# BE200_QUAD_Rev1.net
KiCad netlist of a schematic drawn in EAGLE
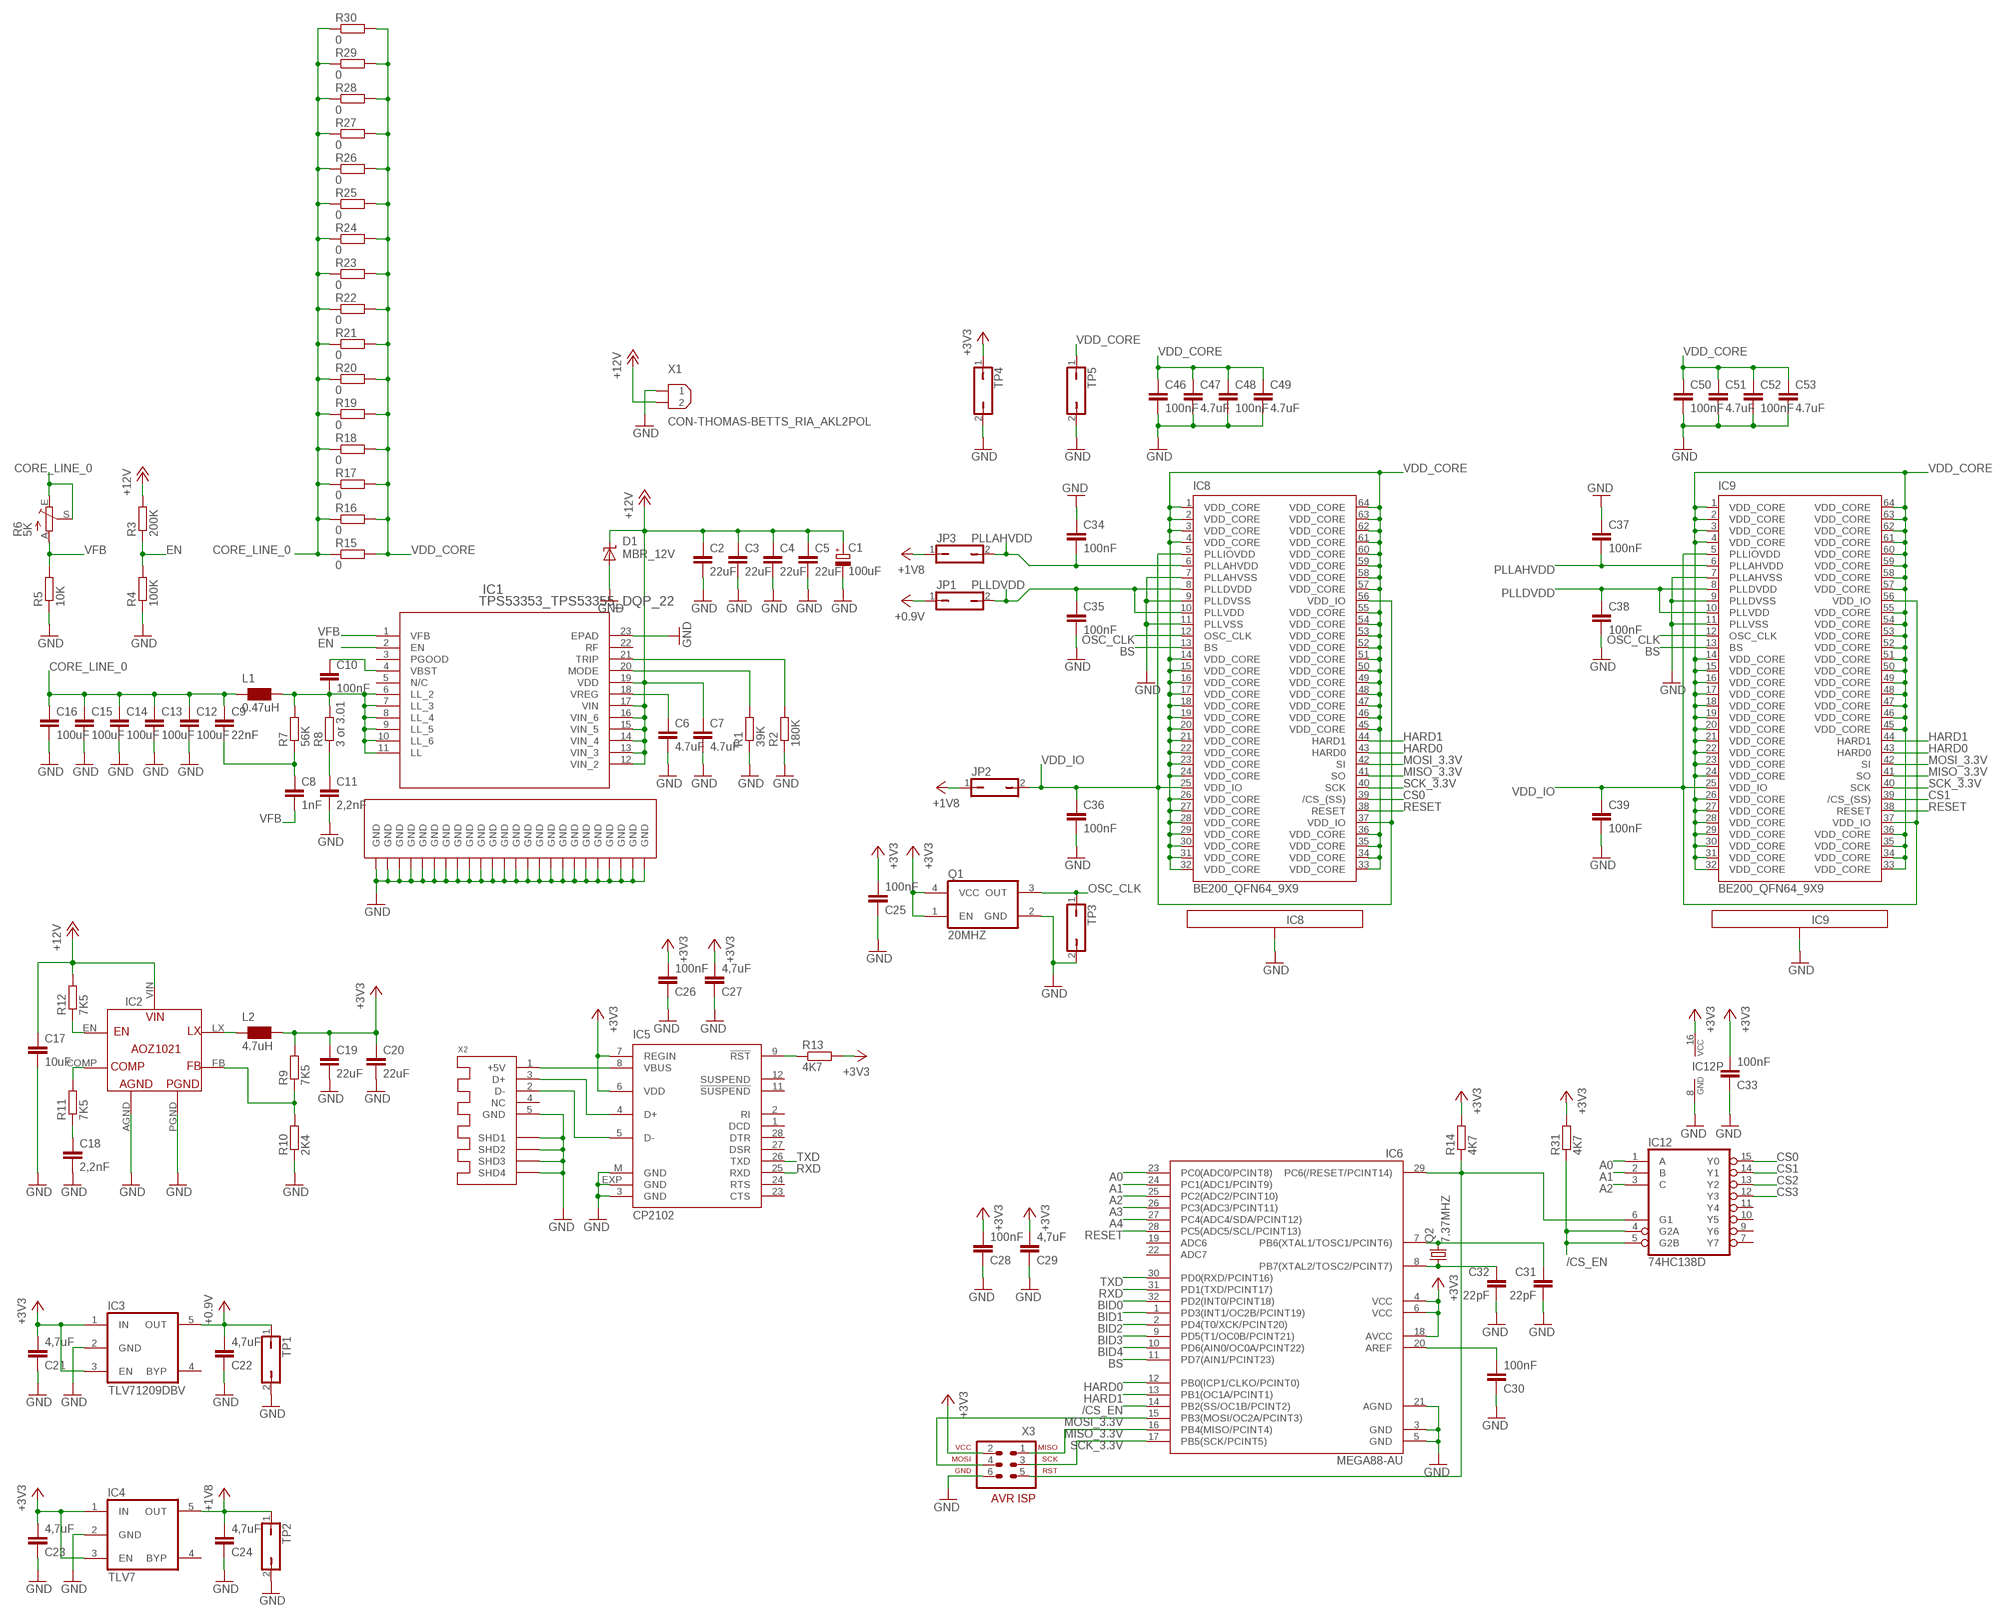
[diagram p0: schematic, sheet 1, part 1 of 2]
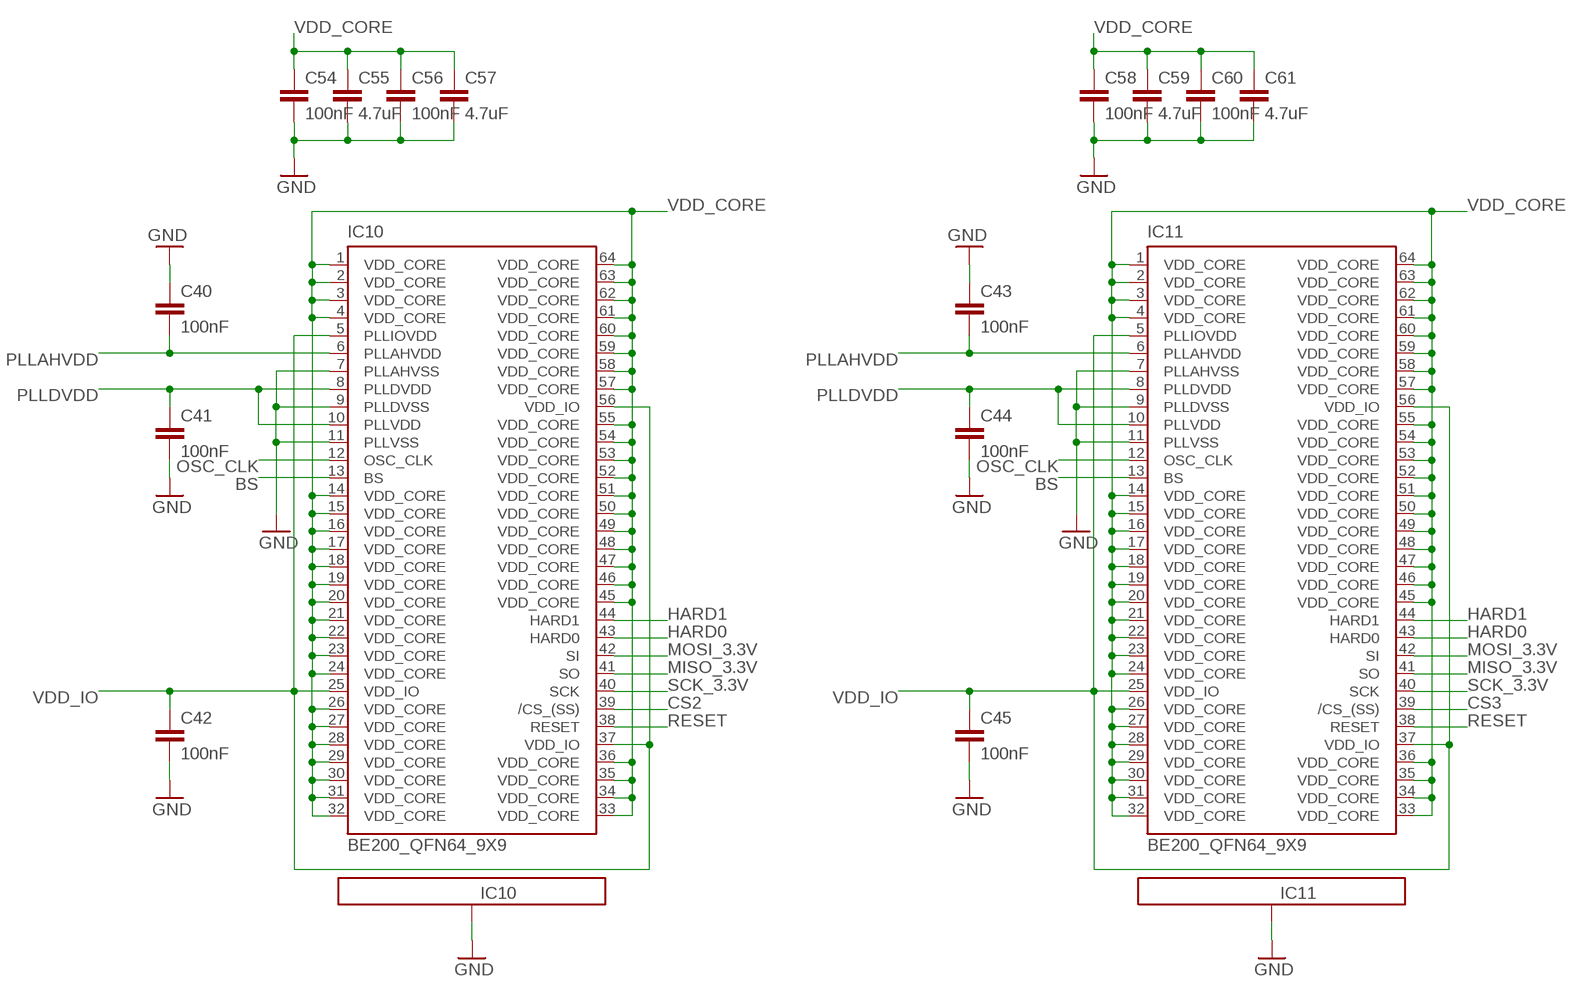
[diagram p1: schematic, sheet 1, part 2 of 2]

(export (version "E")
  (design (tool "Eeschema 10.0.6"))
  (components
    (comp (ref "C1")
      (value "100uF")
      (footprint "eagle-import:153CLV-0605")
      (libsource (lib "eagle-import") (part "CPOL-EU153CLV-0605"))
    )
    (comp (ref "C2")
      (value "22uF")
      (footprint "eagle-import:C1210K")
      (libsource (lib "eagle-import") (part "C-EUC1210K"))
    )
    (comp (ref "C3")
      (value "22uF")
      (footprint "eagle-import:C1210K")
      (libsource (lib "eagle-import") (part "C-EUC1210K"))
    )
    (comp (ref "C4")
      (value "22uF")
      (footprint "eagle-import:C1210K")
      (libsource (lib "eagle-import") (part "C-EUC1210K"))
    )
    (comp (ref "C5")
      (value "22uF")
      (footprint "eagle-import:C1210K")
      (libsource (lib "eagle-import") (part "C-EUC1210K"))
    )
    (comp (ref "C6")
      (value "4.7uF")
      (footprint "eagle-import:C0805K")
      (libsource (lib "eagle-import") (part "C-EUC0805K"))
    )
    (comp (ref "C7")
      (value "4.7uF")
      (footprint "eagle-import:C0805K")
      (libsource (lib "eagle-import") (part "C-EUC0805K"))
    )
    (comp (ref "C8")
      (value "1nF")
      (footprint "eagle-import:C0805K")
      (libsource (lib "eagle-import") (part "C-EUC0805K"))
    )
    (comp (ref "C9")
      (value "22nF")
      (footprint "eagle-import:C0805K")
      (libsource (lib "eagle-import") (part "C-EUC0805K"))
    )
    (comp (ref "C10")
      (value "100nF")
      (footprint "eagle-import:C0805K")
      (libsource (lib "eagle-import") (part "C-EUC0805K"))
    )
    (comp (ref "C11")
      (value "2,2nF")
      (footprint "eagle-import:C0805K")
      (libsource (lib "eagle-import") (part "C-EUC0805K"))
    )
    (comp (ref "C12")
      (value "100uF")
      (footprint "eagle-import:C1210K")
      (libsource (lib "eagle-import") (part "C-EUC1210K"))
    )
    (comp (ref "C13")
      (value "100uF")
      (footprint "eagle-import:C1210K")
      (libsource (lib "eagle-import") (part "C-EUC1210K"))
    )
    (comp (ref "C14")
      (value "100uF")
      (footprint "eagle-import:C1210K")
      (libsource (lib "eagle-import") (part "C-EUC1210K"))
    )
    (comp (ref "C15")
      (value "100uF")
      (footprint "eagle-import:C1210K")
      (libsource (lib "eagle-import") (part "C-EUC1210K"))
    )
    (comp (ref "C16")
      (value "100uF")
      (footprint "eagle-import:C1210K")
      (libsource (lib "eagle-import") (part "C-EUC1210K"))
    )
    (comp (ref "C17")
      (value "10uF")
      (footprint "eagle-import:C1206K")
      (libsource (lib "eagle-import") (part "C-EUC1206K"))
    )
    (comp (ref "C18")
      (value "2,2nF")
      (footprint "eagle-import:C0805K")
      (libsource (lib "eagle-import") (part "C-EUC0805K"))
    )
    (comp (ref "C19")
      (value "22uF")
      (footprint "eagle-import:C1206K")
      (libsource (lib "eagle-import") (part "C-EUC1206K"))
    )
    (comp (ref "C20")
      (value "22uF")
      (footprint "eagle-import:C1206K")
      (libsource (lib "eagle-import") (part "C-EUC1206K"))
    )
    (comp (ref "C21")
      (value "4,7uF")
      (footprint "eagle-import:C0805K")
      (libsource (lib "eagle-import") (part "C-EUC0805K"))
    )
    (comp (ref "C22")
      (value "4,7uF")
      (footprint "eagle-import:C0805K")
      (libsource (lib "eagle-import") (part "C-EUC0805K"))
    )
    (comp (ref "C23")
      (value "4,7uF")
      (footprint "eagle-import:C0805K")
      (libsource (lib "eagle-import") (part "C-EUC0805K"))
    )
    (comp (ref "C24")
      (value "4,7uF")
      (footprint "eagle-import:C0805K")
      (libsource (lib "eagle-import") (part "C-EUC0805K"))
    )
    (comp (ref "C25")
      (value "100nF")
      (footprint "eagle-import:C0805K")
      (libsource (lib "eagle-import") (part "C-EUC0805K"))
    )
    (comp (ref "C26")
      (value "100nF")
      (footprint "eagle-import:C0805K")
      (libsource (lib "eagle-import") (part "C-EUC0805K"))
    )
    (comp (ref "C27")
      (value "4,7uF")
      (footprint "eagle-import:C0805K")
      (libsource (lib "eagle-import") (part "C-EUC0805K"))
    )
    (comp (ref "C28")
      (value "100nF")
      (footprint "eagle-import:C0805K")
      (libsource (lib "eagle-import") (part "C-EUC0805K"))
    )
    (comp (ref "C29")
      (value "4,7uF")
      (footprint "eagle-import:C0805K")
      (libsource (lib "eagle-import") (part "C-EUC0805K"))
    )
    (comp (ref "C30")
      (value "100nF")
      (footprint "eagle-import:C0805K")
      (libsource (lib "eagle-import") (part "C-EUC0805K"))
    )
    (comp (ref "C31")
      (value "22pF")
      (footprint "eagle-import:C0805K")
      (libsource (lib "eagle-import") (part "C-EUC0805K"))
    )
    (comp (ref "C32")
      (value "22pF")
      (footprint "eagle-import:C0805K")
      (libsource (lib "eagle-import") (part "C-EUC0805K"))
    )
    (comp (ref "C33")
      (value "100nF")
      (footprint "eagle-import:C0805K")
      (libsource (lib "eagle-import") (part "C-EUC0805K"))
    )
    (comp (ref "C34")
      (value "100nF")
      (footprint "eagle-import:MYRCL_C0603K")
      (libsource (lib "eagle-import") (part "MYRCL_C-EUC0603K"))
    )
    (comp (ref "C35")
      (value "100nF")
      (footprint "eagle-import:MYRCL_C0603K")
      (libsource (lib "eagle-import") (part "MYRCL_C-EUC0603K"))
    )
    (comp (ref "C36")
      (value "100nF")
      (footprint "eagle-import:MYRCL_C0603K")
      (libsource (lib "eagle-import") (part "MYRCL_C-EUC0603K"))
    )
    (comp (ref "C37")
      (value "100nF")
      (footprint "eagle-import:MYRCL_C0603K")
      (libsource (lib "eagle-import") (part "MYRCL_C-EUC0603K"))
    )
    (comp (ref "C38")
      (value "100nF")
      (footprint "eagle-import:MYRCL_C0603K")
      (libsource (lib "eagle-import") (part "MYRCL_C-EUC0603K"))
    )
    (comp (ref "C39")
      (value "100nF")
      (footprint "eagle-import:MYRCL_C0603K")
      (libsource (lib "eagle-import") (part "MYRCL_C-EUC0603K"))
    )
    (comp (ref "C40")
      (value "100nF")
      (footprint "eagle-import:MYRCL_C0603K")
      (libsource (lib "eagle-import") (part "MYRCL_C-EUC0603K"))
    )
    (comp (ref "C41")
      (value "100nF")
      (footprint "eagle-import:MYRCL_C0603K")
      (libsource (lib "eagle-import") (part "MYRCL_C-EUC0603K"))
    )
    (comp (ref "C42")
      (value "100nF")
      (footprint "eagle-import:MYRCL_C0603K")
      (libsource (lib "eagle-import") (part "MYRCL_C-EUC0603K"))
    )
    (comp (ref "C43")
      (value "100nF")
      (footprint "eagle-import:MYRCL_C0603K")
      (libsource (lib "eagle-import") (part "MYRCL_C-EUC0603K"))
    )
    (comp (ref "C44")
      (value "100nF")
      (footprint "eagle-import:MYRCL_C0603K")
      (libsource (lib "eagle-import") (part "MYRCL_C-EUC0603K"))
    )
    (comp (ref "C45")
      (value "100nF")
      (footprint "eagle-import:MYRCL_C0603K")
      (libsource (lib "eagle-import") (part "MYRCL_C-EUC0603K"))
    )
    (comp (ref "C46")
      (value "100nF")
      (footprint "eagle-import:MYRCL_C0603K")
      (libsource (lib "eagle-import") (part "MYRCL_C-EUC0603K"))
    )
    (comp (ref "C47")
      (value "4.7uF")
      (footprint "eagle-import:MYRCL_C0603K")
      (libsource (lib "eagle-import") (part "MYRCL_C-EUC0603K"))
    )
    (comp (ref "C48")
      (value "100nF")
      (footprint "eagle-import:MYRCL_C0603K")
      (libsource (lib "eagle-import") (part "MYRCL_C-EUC0603K"))
    )
    (comp (ref "C49")
      (value "4.7uF")
      (footprint "eagle-import:MYRCL_C0603K")
      (libsource (lib "eagle-import") (part "MYRCL_C-EUC0603K"))
    )
    (comp (ref "C50")
      (value "100nF")
      (footprint "eagle-import:MYRCL_C0603K")
      (libsource (lib "eagle-import") (part "MYRCL_C-EUC0603K"))
    )
    (comp (ref "C51")
      (value "4.7uF")
      (footprint "eagle-import:MYRCL_C0603K")
      (libsource (lib "eagle-import") (part "MYRCL_C-EUC0603K"))
    )
    (comp (ref "C52")
      (value "100nF")
      (footprint "eagle-import:MYRCL_C0603K")
      (libsource (lib "eagle-import") (part "MYRCL_C-EUC0603K"))
    )
    (comp (ref "C53")
      (value "4.7uF")
      (footprint "eagle-import:MYRCL_C0603K")
      (libsource (lib "eagle-import") (part "MYRCL_C-EUC0603K"))
    )
    (comp (ref "C54")
      (value "100nF")
      (footprint "eagle-import:MYRCL_C0603K")
      (libsource (lib "eagle-import") (part "MYRCL_C-EUC0603K"))
    )
    (comp (ref "C55")
      (value "4.7uF")
      (footprint "eagle-import:MYRCL_C0603K")
      (libsource (lib "eagle-import") (part "MYRCL_C-EUC0603K"))
    )
    (comp (ref "C56")
      (value "100nF")
      (footprint "eagle-import:MYRCL_C0603K")
      (libsource (lib "eagle-import") (part "MYRCL_C-EUC0603K"))
    )
    (comp (ref "C57")
      (value "4.7uF")
      (footprint "eagle-import:MYRCL_C0603K")
      (libsource (lib "eagle-import") (part "MYRCL_C-EUC0603K"))
    )
    (comp (ref "C58")
      (value "100nF")
      (footprint "eagle-import:MYRCL_C0603K")
      (libsource (lib "eagle-import") (part "MYRCL_C-EUC0603K"))
    )
    (comp (ref "C59")
      (value "4.7uF")
      (footprint "eagle-import:MYRCL_C0603K")
      (libsource (lib "eagle-import") (part "MYRCL_C-EUC0603K"))
    )
    (comp (ref "C60")
      (value "100nF")
      (footprint "eagle-import:MYRCL_C0603K")
      (libsource (lib "eagle-import") (part "MYRCL_C-EUC0603K"))
    )
    (comp (ref "C61")
      (value "4.7uF")
      (footprint "eagle-import:MYRCL_C0603K")
      (libsource (lib "eagle-import") (part "MYRCL_C-EUC0603K"))
    )
    (comp (ref "D1")
      (value "MBR_12V")
      (footprint "eagle-import:SMBJ")
      (libsource (lib "eagle-import") (part "SUPPRESSOR-SMBJ"))
    )
    (comp (ref "IC1")
      (value "TPS53353_TPS53355_DQP_22")
      (footprint "eagle-import:DQP22_5P479X3P24")
      (fields
        (field (name "GENERIC_PART_NUMBER") "TPS53355")
        (field (name "MANUFACTURER") "Texas Instruments")
        (field (name "MANUFACTURER_PART_NUMBER") "tps53355_dqp_22")
      )
      (libsource (lib "eagle-import") (part "TPS53355_DQP_22"))
    )
    (comp (ref "IC2")
      (value "AOZ1021")
      (footprint "eagle-import:AOZ1021")
      (libsource (lib "eagle-import") (part "AOZ1021"))
    )
    (comp (ref "IC3")
      (value "TLV71209DBV")
      (footprint "eagle-import:SOT-23-5")
      (libsource (lib "eagle-import") (part "VREG_5PINS-SOT-23-5"))
    )
    (comp (ref "IC4")
      (value "TLV7")
      (footprint "eagle-import:SOT-23-5")
      (libsource (lib "eagle-import") (part "VREG_5PINS-SOT-23-5"))
    )
    (comp (ref "IC5")
      (value "CP2102")
      (footprint "eagle-import:SILABS2_MLP28")
      (libsource (lib "eagle-import") (part "SILABS2_CP2102"))
    )
    (comp (ref "IC6")
      (value "MEGA88-AU")
      (footprint "eagle-import:TQFP32-08")
      (libsource (lib "eagle-import") (part "MEGA48/88/168-AU"))
    )
    (comp (ref "IC8")
      (value "BE200_QFN64_9X9")
      (footprint "eagle-import:QFN64-9X9")
      (libsource (lib "eagle-import") (part "BE200_QFN64_9X9"))
    )
    (comp (ref "IC9")
      (value "BE200_QFN64_9X9")
      (footprint "eagle-import:QFN64-9X9")
      (libsource (lib "eagle-import") (part "BE200_QFN64_9X9"))
    )
    (comp (ref "IC10")
      (value "BE200_QFN64_9X9")
      (footprint "eagle-import:QFN64-9X9")
      (libsource (lib "eagle-import") (part "BE200_QFN64_9X9"))
    )
    (comp (ref "IC11")
      (value "BE200_QFN64_9X9")
      (footprint "eagle-import:QFN64-9X9")
      (libsource (lib "eagle-import") (part "BE200_QFN64_9X9"))
    )
    (comp (ref "IC12")
      (value "74HC138D")
      (footprint "eagle-import:SO16")
      (libsource (lib "eagle-import") (part "74138DHC"))
    )
    (comp (ref "JP1")
      (value "JP1Q")
      (footprint "eagle-import:JP1")
      (libsource (lib "eagle-import") (part "JP1Q"))
    )
    (comp (ref "JP2")
      (value "JP1Q")
      (footprint "eagle-import:JP1")
      (libsource (lib "eagle-import") (part "JP1Q"))
    )
    (comp (ref "JP3")
      (value "JP1Q")
      (footprint "eagle-import:JP1")
      (libsource (lib "eagle-import") (part "JP1Q"))
    )
    (comp (ref "L1")
      (value "0.47uH")
      (footprint "eagle-import:INDUCTOR_PA0513")
      (libsource (lib "eagle-import") (part "INDCUTOR_PA0513"))
    )
    (comp (ref "L2")
      (value "4.7uH")
      (footprint "eagle-import:INDCUCTOR_7.3X7.3")
      (libsource (lib "eagle-import") (part "INDUCTOR_7.3X7.3"))
    )
    (comp (ref "Q1")
      (value "20MHZ")
      (footprint "eagle-import:OSCILLATOR_7X5_SMD")
      (libsource (lib "eagle-import") (part "OSC-OSCILLATOR"))
    )
    (comp (ref "Q2")
      (value "7.37MHZ")
      (footprint "eagle-import:HC49UP")
      (libsource (lib "eagle-import") (part "CRYSTALHC49UP"))
    )
    (comp (ref "R1")
      (value "39K")
      (footprint "eagle-import:R0805K")
      (libsource (lib "eagle-import") (part "R-EU_R0805K"))
    )
    (comp (ref "R2")
      (value "180K")
      (footprint "eagle-import:R0805K")
      (libsource (lib "eagle-import") (part "R-EU_R0805K"))
    )
    (comp (ref "R3")
      (value "200K")
      (footprint "eagle-import:R0805K")
      (libsource (lib "eagle-import") (part "R-EU_R0805K"))
    )
    (comp (ref "R4")
      (value "100K")
      (footprint "eagle-import:R0805K")
      (libsource (lib "eagle-import") (part "R-EU_R0805K"))
    )
    (comp (ref "R5")
      (value "10K")
      (footprint "eagle-import:R0805K")
      (libsource (lib "eagle-import") (part "R-EU_R0805K"))
    )
    (comp (ref "R6")
      (value "5K")
      (footprint "eagle-import:S64W")
      (libsource (lib "eagle-import") (part "TRIM_EU-S64W"))
    )
    (comp (ref "R7")
      (value "56K")
      (footprint "eagle-import:R0805K")
      (libsource (lib "eagle-import") (part "R-EU_R0805K"))
    )
    (comp (ref "R8")
      (value "3 or 3.01")
      (footprint "eagle-import:R0805K")
      (libsource (lib "eagle-import") (part "R-EU_R0805K"))
    )
    (comp (ref "R9")
      (value "7K5")
      (footprint "eagle-import:R0805K")
      (libsource (lib "eagle-import") (part "R-EU_R0805K"))
    )
    (comp (ref "R10")
      (value "2K4")
      (footprint "eagle-import:R0805K")
      (libsource (lib "eagle-import") (part "R-EU_R0805K"))
    )
    (comp (ref "R11")
      (value "7K5")
      (footprint "eagle-import:R0805K")
      (libsource (lib "eagle-import") (part "R-EU_R0805K"))
    )
    (comp (ref "R12")
      (value "7K5")
      (footprint "eagle-import:R0805K")
      (libsource (lib "eagle-import") (part "R-EU_R0805K"))
    )
    (comp (ref "R13")
      (value "4K7")
      (footprint "eagle-import:R0805K")
      (libsource (lib "eagle-import") (part "R-EU_R0805K"))
    )
    (comp (ref "R14")
      (value "4K7")
      (footprint "eagle-import:R0805K")
      (libsource (lib "eagle-import") (part "R-EU_R0805K"))
    )
    (comp (ref "R15")
      (value "0")
      (footprint "eagle-import:R0805K")
      (libsource (lib "eagle-import") (part "R-EU_R0805K"))
    )
    (comp (ref "R16")
      (value "0")
      (footprint "eagle-import:R0805K")
      (libsource (lib "eagle-import") (part "R-EU_R0805K"))
    )
    (comp (ref "R17")
      (value "0")
      (footprint "eagle-import:R0805K")
      (libsource (lib "eagle-import") (part "R-EU_R0805K"))
    )
    (comp (ref "R18")
      (value "0")
      (footprint "eagle-import:R0805K")
      (libsource (lib "eagle-import") (part "R-EU_R0805K"))
    )
    (comp (ref "R19")
      (value "0")
      (footprint "eagle-import:R0805K")
      (libsource (lib "eagle-import") (part "R-EU_R0805K"))
    )
    (comp (ref "R20")
      (value "0")
      (footprint "eagle-import:R0805K")
      (libsource (lib "eagle-import") (part "R-EU_R0805K"))
    )
    (comp (ref "R21")
      (value "0")
      (footprint "eagle-import:R0805K")
      (libsource (lib "eagle-import") (part "R-EU_R0805K"))
    )
    (comp (ref "R22")
      (value "0")
      (footprint "eagle-import:R0805K")
      (libsource (lib "eagle-import") (part "R-EU_R0805K"))
    )
    (comp (ref "R23")
      (value "0")
      (footprint "eagle-import:R0805K")
      (libsource (lib "eagle-import") (part "R-EU_R0805K"))
    )
    (comp (ref "R24")
      (value "0")
      (footprint "eagle-import:R0805K")
      (libsource (lib "eagle-import") (part "R-EU_R0805K"))
    )
    (comp (ref "R25")
      (value "0")
      (footprint "eagle-import:R0805K")
      (libsource (lib "eagle-import") (part "R-EU_R0805K"))
    )
    (comp (ref "R26")
      (value "0")
      (footprint "eagle-import:R0805K")
      (libsource (lib "eagle-import") (part "R-EU_R0805K"))
    )
    (comp (ref "R27")
      (value "0")
      (footprint "eagle-import:R0805K")
      (libsource (lib "eagle-import") (part "R-EU_R0805K"))
    )
    (comp (ref "R28")
      (value "0")
      (footprint "eagle-import:R0805K")
      (libsource (lib "eagle-import") (part "R-EU_R0805K"))
    )
    (comp (ref "R29")
      (value "0")
      (footprint "eagle-import:R0805K")
      (libsource (lib "eagle-import") (part "R-EU_R0805K"))
    )
    (comp (ref "R30")
      (value "0")
      (footprint "eagle-import:R0805K")
      (libsource (lib "eagle-import") (part "R-EU_R0805K"))
    )
    (comp (ref "R31")
      (value "4K7")
      (footprint "eagle-import:R0805K")
      (libsource (lib "eagle-import") (part "R-EU_R0805K"))
    )
    (comp (ref "TP1")
      (value "JP1Q")
      (footprint "eagle-import:JP1")
      (libsource (lib "eagle-import") (part "JP1Q"))
    )
    (comp (ref "TP2")
      (value "JP1Q")
      (footprint "eagle-import:JP1")
      (libsource (lib "eagle-import") (part "JP1Q"))
    )
    (comp (ref "TP3")
      (value "JP1Q")
      (footprint "eagle-import:JP1")
      (libsource (lib "eagle-import") (part "JP1Q"))
    )
    (comp (ref "TP4")
      (value "JP1Q")
      (footprint "eagle-import:JP1")
      (libsource (lib "eagle-import") (part "JP1Q"))
    )
    (comp (ref "TP5")
      (value "JP1Q")
      (footprint "eagle-import:JP1")
      (libsource (lib "eagle-import") (part "JP1Q"))
    )
    (comp (ref "X1")
      (value "CON-THOMAS-BETTS_RIA_AKL2POL")
      (footprint "eagle-import:CON-THOMAS-BETTS_RIA_AKL2POL")
      (libsource (lib "eagle-import") (part "CON-THOMAS-BETTS_RIA_AKL2POL"))
    )
    (comp (ref "X2")
      (value "MYSTUFF_USB-MINI-ASSMANN")
      (footprint "eagle-import:MYSTUFF_USB_MINI-ASSMANN")
      (libsource (lib "eagle-import") (part "MYSTUFF_USB-MINI-ASSMANN"))
    )
    (comp (ref "X3")
      (value "AVR-ISP-6VERT")
      (footprint "eagle-import:AVR-ISP-6")
      (libsource (lib "eagle-import") (part "AVR-ISP-6VERT"))
    )
  )
  (nets
    (net (code "1") (name "+0.9V") (class "Default")
      (node (ref "C22") (pin "2") (pinfunction "2_2") (pintype "passive"))
      (node (ref "IC3") (pin "5") (pinfunction "OUT_5") (pintype "bidirectional"))
      (node (ref "JP1") (pin "1") (pinfunction "1_1") (pintype "passive"))
      (node (ref "TP1") (pin "1") (pinfunction "1_1") (pintype "passive"))
    )
    (net (code "2") (name "+1V8") (class "Default")
      (node (ref "C24") (pin "2") (pinfunction "2_2") (pintype "passive"))
      (node (ref "IC4") (pin "5") (pinfunction "OUT_5") (pintype "bidirectional"))
      (node (ref "JP2") (pin "1") (pinfunction "1_1") (pintype "passive"))
      (node (ref "JP3") (pin "1") (pinfunction "1_1") (pintype "passive"))
      (node (ref "TP2") (pin "1") (pinfunction "1_1") (pintype "passive"))
    )
    (net (code "3") (name "+3V3") (class "Default")
      (node (ref "C19") (pin "1") (pinfunction "1_1") (pintype "passive"))
      (node (ref "C20") (pin "1") (pinfunction "1_1") (pintype "passive"))
      (node (ref "C21") (pin "2") (pinfunction "2_2") (pintype "passive"))
      (node (ref "C23") (pin "2") (pinfunction "2_2") (pintype "passive"))
      (node (ref "C25") (pin "2") (pinfunction "2_2") (pintype "passive"))
      (node (ref "C26") (pin "2") (pinfunction "2_2") (pintype "passive"))
      (node (ref "C27") (pin "2") (pinfunction "2_2") (pintype "passive"))
      (node (ref "C28") (pin "2") (pinfunction "2_2") (pintype "passive"))
      (node (ref "C29") (pin "2") (pinfunction "2_2") (pintype "passive"))
      (node (ref "C33") (pin "2") (pinfunction "2_2") (pintype "passive"))
      (node (ref "IC12") (pin "16") (pinfunction "VCC_16") (pintype "power_in"))
      (node (ref "IC3") (pin "1") (pinfunction "IN_1") (pintype "bidirectional"))
      (node (ref "IC3") (pin "3") (pinfunction "EN_3") (pintype "bidirectional"))
      (node (ref "IC4") (pin "1") (pinfunction "IN_1") (pintype "bidirectional"))
      (node (ref "IC4") (pin "3") (pinfunction "EN_3") (pintype "bidirectional"))
      (node (ref "IC5") (pin "6") (pinfunction "VDD_6") (pintype "power_in"))
      (node (ref "IC5") (pin "7") (pinfunction "REGIN_7") (pintype "passive"))
      (node (ref "IC6") (pin "18") (pinfunction "AVCC_18") (pintype "passive"))
      (node (ref "IC6") (pin "4") (pinfunction "VCC_4") (pintype "power_in"))
      (node (ref "IC6") (pin "6") (pinfunction "VCC_6") (pintype "power_in"))
      (node (ref "L2") (pin "2") (pinfunction "2_2") (pintype "passive"))
      (node (ref "Q1") (pin "1") (pinfunction "EN_1") (pintype "input"))
      (node (ref "Q1") (pin "4") (pinfunction "VCC_4") (pintype "power_in"))
      (node (ref "R13") (pin "2") (pinfunction "2_2") (pintype "passive"))
      (node (ref "R14") (pin "2") (pinfunction "2_2") (pintype "passive"))
      (node (ref "R31") (pin "2") (pinfunction "2_2") (pintype "passive"))
      (node (ref "R9") (pin "2") (pinfunction "2_2") (pintype "passive"))
      (node (ref "TP4") (pin "1") (pinfunction "1_1") (pintype "passive"))
      (node (ref "X3") (pin "2") (pinfunction "2_2") (pintype "passive"))
    )
    (net (code "4") (name "+12V") (class "Default")
      (node (ref "C1") (pin "+") (pinfunction "+_+") (pintype "passive"))
      (node (ref "C17") (pin "1") (pinfunction "1_1") (pintype "passive"))
      (node (ref "C2") (pin "1") (pinfunction "1_1") (pintype "passive"))
      (node (ref "C3") (pin "1") (pinfunction "1_1") (pintype "passive"))
      (node (ref "C4") (pin "1") (pinfunction "1_1") (pintype "passive"))
      (node (ref "C5") (pin "1") (pinfunction "1_1") (pintype "passive"))
      (node (ref "C7") (pin "1") (pinfunction "1_1") (pintype "passive"))
      (node (ref "D1") (pin "C") (pinfunction "C_C") (pintype "passive"))
      (node (ref "IC1") (pin "12") (pinfunction "VIN_2_12") (pintype "input"))
      (node (ref "IC1") (pin "13") (pinfunction "VIN_3_13") (pintype "input"))
      (node (ref "IC1") (pin "14") (pinfunction "VIN_4_14") (pintype "input"))
      (node (ref "IC1") (pin "15") (pinfunction "VIN_5_15") (pintype "input"))
      (node (ref "IC1") (pin "16") (pinfunction "VIN_6_16") (pintype "input"))
      (node (ref "IC1") (pin "17") (pinfunction "VIN_17") (pintype "input"))
      (node (ref "IC1") (pin "19") (pinfunction "VDD_19") (pintype "power_in"))
      (node (ref "IC2") (pin "VIN") (pinfunction "VIN_VIN") (pintype "bidirectional"))
      (node (ref "R12") (pin "2") (pinfunction "2_2") (pintype "passive"))
      (node (ref "R3") (pin "2") (pinfunction "2_2") (pintype "passive"))
      (node (ref "X1") (pin "2") (pinfunction "2_2") (pintype "passive"))
    )
    (net (code "5") (name "/A0") (class "Default")
      (node (ref "IC12") (pin "1") (pinfunction "A_1") (pintype "input"))
      (node (ref "IC6") (pin "23") (pinfunction "PC0(ADC0/PCINT8)_23") (pintype "bidirectional"))
    )
    (net (code "6") (name "/A1") (class "Default")
      (node (ref "IC12") (pin "2") (pinfunction "B_2") (pintype "input"))
      (node (ref "IC6") (pin "24") (pinfunction "PC1(ADC1/PCINT9)_24") (pintype "bidirectional"))
    )
    (net (code "7") (name "/A2") (class "Default")
      (node (ref "IC12") (pin "3") (pinfunction "C_3") (pintype "input"))
      (node (ref "IC6") (pin "25") (pinfunction "PC2(ADC2/PCINT10)_25") (pintype "bidirectional"))
    )
    (net (code "8") (name "/A3") (class "Default")
      (node (ref "IC6") (pin "26") (pinfunction "PC3(ADC3/PCINT11)_26") (pintype "bidirectional"))
    )
    (net (code "9") (name "/A4") (class "Default")
      (node (ref "IC6") (pin "27") (pinfunction "PC4(ADC4/SDA/PCINT12)_27") (pintype "bidirectional"))
    )
    (net (code "10") (name "/BID0") (class "Default")
      (node (ref "IC6") (pin "32") (pinfunction "PD2(INT0/PCINT18)_32") (pintype "bidirectional"))
    )
    (net (code "11") (name "/BID1") (class "Default")
      (node (ref "IC6") (pin "1") (pinfunction "PD3(INT1/OC2B/PCINT19)_1") (pintype "bidirectional"))
    )
    (net (code "12") (name "/BID2") (class "Default")
      (node (ref "IC6") (pin "2") (pinfunction "PD4(T0/XCK/PCINT20)_2") (pintype "bidirectional"))
    )
    (net (code "13") (name "/BID3") (class "Default")
      (node (ref "IC6") (pin "9") (pinfunction "PD5(T1/OC0B/PCINT21)_9") (pintype "bidirectional"))
    )
    (net (code "14") (name "/BID4") (class "Default")
      (node (ref "IC6") (pin "10") (pinfunction "PD6(AIN0/OC0A/PCINT22)_10") (pintype "bidirectional"))
    )
    (net (code "15") (name "/BS") (class "Default")
      (node (ref "IC10") (pin "13") (pinfunction "BS_13") (pintype "input"))
      (node (ref "IC11") (pin "13") (pinfunction "BS_13") (pintype "input"))
      (node (ref "IC6") (pin "11") (pinfunction "PD7(AIN1/PCINT23)_11") (pintype "bidirectional"))
      (node (ref "IC8") (pin "13") (pinfunction "BS_13") (pintype "input"))
      (node (ref "IC9") (pin "13") (pinfunction "BS_13") (pintype "input"))
    )
    (net (code "16") (name "/CORE_LINE_0") (class "Default")
      (node (ref "C12") (pin "1") (pinfunction "1_1") (pintype "passive"))
      (node (ref "C13") (pin "1") (pinfunction "1_1") (pintype "passive"))
      (node (ref "C14") (pin "1") (pinfunction "1_1") (pintype "passive"))
      (node (ref "C15") (pin "1") (pinfunction "1_1") (pintype "passive"))
      (node (ref "C16") (pin "1") (pinfunction "1_1") (pintype "passive"))
      (node (ref "C9") (pin "1") (pinfunction "1_1") (pintype "passive"))
      (node (ref "L1") (pin "1") (pinfunction "1_1") (pintype "passive"))
      (node (ref "R15") (pin "1") (pinfunction "1_1") (pintype "passive"))
      (node (ref "R16") (pin "1") (pinfunction "1_1") (pintype "passive"))
      (node (ref "R17") (pin "1") (pinfunction "1_1") (pintype "passive"))
      (node (ref "R18") (pin "1") (pinfunction "1_1") (pintype "passive"))
      (node (ref "R19") (pin "1") (pinfunction "1_1") (pintype "passive"))
      (node (ref "R20") (pin "1") (pinfunction "1_1") (pintype "passive"))
      (node (ref "R21") (pin "1") (pinfunction "1_1") (pintype "passive"))
      (node (ref "R22") (pin "1") (pinfunction "1_1") (pintype "passive"))
      (node (ref "R23") (pin "1") (pinfunction "1_1") (pintype "passive"))
      (node (ref "R24") (pin "1") (pinfunction "1_1") (pintype "passive"))
      (node (ref "R25") (pin "1") (pinfunction "1_1") (pintype "passive"))
      (node (ref "R26") (pin "1") (pinfunction "1_1") (pintype "passive"))
      (node (ref "R27") (pin "1") (pinfunction "1_1") (pintype "passive"))
      (node (ref "R28") (pin "1") (pinfunction "1_1") (pintype "passive"))
      (node (ref "R29") (pin "1") (pinfunction "1_1") (pintype "passive"))
      (node (ref "R30") (pin "1") (pinfunction "1_1") (pintype "passive"))
      (node (ref "R6") (pin "E") (pinfunction "E_E") (pintype "passive"))
      (node (ref "R6") (pin "S") (pinfunction "S_S") (pintype "passive"))
    )
    (net (code "17") (name "/CS0") (class "Default")
      (node (ref "IC12") (pin "15") (pinfunction "Y0_15") (pintype "output"))
      (node (ref "IC8") (pin "39") (pinfunction "/CS_(SS)_39") (pintype "input"))
    )
    (net (code "18") (name "/CS1") (class "Default")
      (node (ref "IC12") (pin "14") (pinfunction "Y1_14") (pintype "output"))
      (node (ref "IC9") (pin "39") (pinfunction "/CS_(SS)_39") (pintype "input"))
    )
    (net (code "19") (name "/CS2") (class "Default")
      (node (ref "IC10") (pin "39") (pinfunction "/CS_(SS)_39") (pintype "input"))
      (node (ref "IC12") (pin "13") (pinfunction "Y2_13") (pintype "output"))
    )
    (net (code "20") (name "/CS3") (class "Default")
      (node (ref "IC11") (pin "39") (pinfunction "/CS_(SS)_39") (pintype "input"))
      (node (ref "IC12") (pin "12") (pinfunction "Y3_12") (pintype "output"))
    )
    (net (code "21") (name "/EN") (class "Default")
      (node (ref "IC1") (pin "2") (pinfunction "EN_2") (pintype "input"))
      (node (ref "R3") (pin "1") (pinfunction "1_1") (pintype "passive"))
      (node (ref "R4") (pin "2") (pinfunction "2_2") (pintype "passive"))
    )
    (net (code "22") (name "/HARD0") (class "Default")
      (node (ref "IC10") (pin "43") (pinfunction "HARD0_43") (pintype "input"))
      (node (ref "IC11") (pin "43") (pinfunction "HARD0_43") (pintype "input"))
      (node (ref "IC6") (pin "12") (pinfunction "PB0(ICP1/CLKO/PCINT0)_12") (pintype "bidirectional"))
      (node (ref "IC8") (pin "43") (pinfunction "HARD0_43") (pintype "input"))
      (node (ref "IC9") (pin "43") (pinfunction "HARD0_43") (pintype "input"))
    )
    (net (code "23") (name "/HARD1") (class "Default")
      (node (ref "IC10") (pin "44") (pinfunction "HARD1_44") (pintype "input"))
      (node (ref "IC11") (pin "44") (pinfunction "HARD1_44") (pintype "input"))
      (node (ref "IC6") (pin "13") (pinfunction "PB1(OC1A/PCINT1)_13") (pintype "bidirectional"))
      (node (ref "IC8") (pin "44") (pinfunction "HARD1_44") (pintype "input"))
      (node (ref "IC9") (pin "44") (pinfunction "HARD1_44") (pintype "input"))
    )
    (net (code "24") (name "/MISO_3.3V") (class "Default")
      (node (ref "IC10") (pin "41") (pinfunction "SO_41") (pintype "input"))
      (node (ref "IC11") (pin "41") (pinfunction "SO_41") (pintype "input"))
      (node (ref "IC6") (pin "16") (pinfunction "PB4(MISO/PCINT4)_16") (pintype "bidirectional"))
      (node (ref "IC8") (pin "41") (pinfunction "SO_41") (pintype "input"))
      (node (ref "IC9") (pin "41") (pinfunction "SO_41") (pintype "input"))
      (node (ref "X3") (pin "1") (pinfunction "1_1") (pintype "passive"))
    )
    (net (code "25") (name "/MOSI_3.3V") (class "Default")
      (node (ref "IC10") (pin "42") (pinfunction "SI_42") (pintype "input"))
      (node (ref "IC11") (pin "42") (pinfunction "SI_42") (pintype "input"))
      (node (ref "IC6") (pin "15") (pinfunction "PB3(MOSI/OC2A/PCINT3)_15") (pintype "bidirectional"))
      (node (ref "IC8") (pin "42") (pinfunction "SI_42") (pintype "input"))
      (node (ref "IC9") (pin "42") (pinfunction "SI_42") (pintype "input"))
      (node (ref "X3") (pin "4") (pinfunction "4_4") (pintype "passive"))
    )
    (net (code "26") (name "/OSC_CLK") (class "Default")
      (node (ref "IC10") (pin "12") (pinfunction "OSC_CLK_12") (pintype "input"))
      (node (ref "IC11") (pin "12") (pinfunction "OSC_CLK_12") (pintype "input"))
      (node (ref "IC8") (pin "12") (pinfunction "OSC_CLK_12") (pintype "input"))
      (node (ref "IC9") (pin "12") (pinfunction "OSC_CLK_12") (pintype "input"))
      (node (ref "Q1") (pin "3") (pinfunction "OUT_3") (pintype "output"))
      (node (ref "TP3") (pin "1") (pinfunction "1_1") (pintype "passive"))
    )
    (net (code "27") (name "/PLLAHVDD") (class "Default")
      (node (ref "C34") (pin "2") (pinfunction "2_2") (pintype "passive"))
      (node (ref "C37") (pin "2") (pinfunction "2_2") (pintype "passive"))
      (node (ref "C40") (pin "2") (pinfunction "2_2") (pintype "passive"))
      (node (ref "C43") (pin "2") (pinfunction "2_2") (pintype "passive"))
      (node (ref "IC10") (pin "6") (pinfunction "PLLAHVDD_6") (pintype "power_in"))
      (node (ref "IC11") (pin "6") (pinfunction "PLLAHVDD_6") (pintype "power_in"))
      (node (ref "IC8") (pin "6") (pinfunction "PLLAHVDD_6") (pintype "power_in"))
      (node (ref "IC9") (pin "6") (pinfunction "PLLAHVDD_6") (pintype "power_in"))
      (node (ref "JP3") (pin "2") (pinfunction "2_2") (pintype "passive"))
    )
    (net (code "28") (name "/PLLDVDD") (class "Default")
      (node (ref "C35") (pin "1") (pinfunction "1_1") (pintype "passive"))
      (node (ref "C38") (pin "1") (pinfunction "1_1") (pintype "passive"))
      (node (ref "C41") (pin "1") (pinfunction "1_1") (pintype "passive"))
      (node (ref "C44") (pin "1") (pinfunction "1_1") (pintype "passive"))
      (node (ref "IC10") (pin "10") (pinfunction "PLLVDD_10") (pintype "power_in"))
      (node (ref "IC10") (pin "8") (pinfunction "PLLDVDD_8") (pintype "power_in"))
      (node (ref "IC11") (pin "10") (pinfunction "PLLVDD_10") (pintype "power_in"))
      (node (ref "IC11") (pin "8") (pinfunction "PLLDVDD_8") (pintype "power_in"))
      (node (ref "IC8") (pin "10") (pinfunction "PLLVDD_10") (pintype "power_in"))
      (node (ref "IC8") (pin "8") (pinfunction "PLLDVDD_8") (pintype "power_in"))
      (node (ref "IC9") (pin "10") (pinfunction "PLLVDD_10") (pintype "power_in"))
      (node (ref "IC9") (pin "8") (pinfunction "PLLDVDD_8") (pintype "power_in"))
      (node (ref "JP1") (pin "2") (pinfunction "2_2") (pintype "passive"))
    )
    (net (code "29") (name "/RESET") (class "Default")
      (node (ref "IC10") (pin "38") (pinfunction "RESET_38") (pintype "input"))
      (node (ref "IC11") (pin "38") (pinfunction "RESET_38") (pintype "input"))
      (node (ref "IC6") (pin "28") (pinfunction "PC5(ADC5/SCL/PCINT13)_28") (pintype "bidirectional"))
      (node (ref "IC8") (pin "38") (pinfunction "RESET_38") (pintype "input"))
      (node (ref "IC9") (pin "38") (pinfunction "RESET_38") (pintype "input"))
    )
    (net (code "30") (name "/RXD") (class "Default")
      (node (ref "IC5") (pin "25") (pinfunction "RXD_25") (pintype "input"))
      (node (ref "IC6") (pin "31") (pinfunction "PD1(TXD/PCINT17)_31") (pintype "bidirectional"))
    )
    (net (code "31") (name "/SCK_3.3V") (class "Default")
      (node (ref "IC10") (pin "40") (pinfunction "SCK_40") (pintype "input"))
      (node (ref "IC11") (pin "40") (pinfunction "SCK_40") (pintype "input"))
      (node (ref "IC6") (pin "17") (pinfunction "PB5(SCK/PCINT5)_17") (pintype "bidirectional"))
      (node (ref "IC8") (pin "40") (pinfunction "SCK_40") (pintype "input"))
      (node (ref "IC9") (pin "40") (pinfunction "SCK_40") (pintype "input"))
      (node (ref "X3") (pin "3") (pinfunction "3_3") (pintype "passive"))
    )
    (net (code "32") (name "/TXD") (class "Default")
      (node (ref "IC5") (pin "26") (pinfunction "TXD_26") (pintype "output"))
      (node (ref "IC6") (pin "30") (pinfunction "PD0(RXD/PCINT16)_30") (pintype "bidirectional"))
    )
    (net (code "33") (name "/VDD_CORE") (class "Default")
      (node (ref "C46") (pin "1") (pinfunction "1_1") (pintype "passive"))
      (node (ref "C47") (pin "1") (pinfunction "1_1") (pintype "passive"))
      (node (ref "C48") (pin "1") (pinfunction "1_1") (pintype "passive"))
      (node (ref "C49") (pin "1") (pinfunction "1_1") (pintype "passive"))
      (node (ref "C50") (pin "1") (pinfunction "1_1") (pintype "passive"))
      (node (ref "C51") (pin "1") (pinfunction "1_1") (pintype "passive"))
      (node (ref "C52") (pin "1") (pinfunction "1_1") (pintype "passive"))
      (node (ref "C53") (pin "1") (pinfunction "1_1") (pintype "passive"))
      (node (ref "C54") (pin "1") (pinfunction "1_1") (pintype "passive"))
      (node (ref "C55") (pin "1") (pinfunction "1_1") (pintype "passive"))
      (node (ref "C56") (pin "1") (pinfunction "1_1") (pintype "passive"))
      (node (ref "C57") (pin "1") (pinfunction "1_1") (pintype "passive"))
      (node (ref "C58") (pin "1") (pinfunction "1_1") (pintype "passive"))
      (node (ref "C59") (pin "1") (pinfunction "1_1") (pintype "passive"))
      (node (ref "C60") (pin "1") (pinfunction "1_1") (pintype "passive"))
      (node (ref "C61") (pin "1") (pinfunction "1_1") (pintype "passive"))
      (node (ref "IC10") (pin "1") (pinfunction "VDD_CORE_1") (pintype "power_in"))
      (node (ref "IC10") (pin "14") (pinfunction "VDD_CORE_14") (pintype "power_in"))
      (node (ref "IC10") (pin "15") (pinfunction "VDD_CORE_15") (pintype "power_in"))
      (node (ref "IC10") (pin "16") (pinfunction "VDD_CORE_16") (pintype "power_in"))
      (node (ref "IC10") (pin "17") (pinfunction "VDD_CORE_17") (pintype "power_in"))
      (node (ref "IC10") (pin "18") (pinfunction "VDD_CORE_18") (pintype "power_in"))
      (node (ref "IC10") (pin "19") (pinfunction "VDD_CORE_19") (pintype "power_in"))
      (node (ref "IC10") (pin "2") (pinfunction "VDD_CORE_2") (pintype "power_in"))
      (node (ref "IC10") (pin "20") (pinfunction "VDD_CORE_20") (pintype "power_in"))
      (node (ref "IC10") (pin "21") (pinfunction "VDD_CORE_21") (pintype "power_in"))
      (node (ref "IC10") (pin "22") (pinfunction "VDD_CORE_22") (pintype "power_in"))
      (node (ref "IC10") (pin "23") (pinfunction "VDD_CORE_23") (pintype "power_in"))
      (node (ref "IC10") (pin "24") (pinfunction "VDD_CORE_24") (pintype "power_in"))
      (node (ref "IC10") (pin "26") (pinfunction "VDD_CORE_26") (pintype "power_in"))
      (node (ref "IC10") (pin "27") (pinfunction "VDD_CORE_27") (pintype "power_in"))
      (node (ref "IC10") (pin "28") (pinfunction "VDD_CORE_28") (pintype "power_in"))
      (node (ref "IC10") (pin "29") (pinfunction "VDD_CORE_29") (pintype "power_in"))
      (node (ref "IC10") (pin "3") (pinfunction "VDD_CORE_3") (pintype "power_in"))
      (node (ref "IC10") (pin "30") (pinfunction "VDD_CORE_30") (pintype "power_in"))
      (node (ref "IC10") (pin "31") (pinfunction "VDD_CORE_31") (pintype "power_in"))
      (node (ref "IC10") (pin "32") (pinfunction "VDD_CORE_32") (pintype "power_in"))
      (node (ref "IC10") (pin "33") (pinfunction "VDD_CORE_33") (pintype "power_in"))
      (node (ref "IC10") (pin "34") (pinfunction "VDD_CORE_34") (pintype "power_in"))
      (node (ref "IC10") (pin "35") (pinfunction "VDD_CORE_35") (pintype "power_in"))
      (node (ref "IC10") (pin "36") (pinfunction "VDD_CORE_36") (pintype "power_in"))
      (node (ref "IC10") (pin "4") (pinfunction "VDD_CORE_4") (pintype "power_in"))
      (node (ref "IC10") (pin "45") (pinfunction "VDD_CORE_45") (pintype "power_in"))
      (node (ref "IC10") (pin "46") (pinfunction "VDD_CORE_46") (pintype "power_in"))
      (node (ref "IC10") (pin "47") (pinfunction "VDD_CORE_47") (pintype "power_in"))
      (node (ref "IC10") (pin "48") (pinfunction "VDD_CORE_48") (pintype "power_in"))
      (node (ref "IC10") (pin "49") (pinfunction "VDD_CORE_49") (pintype "power_in"))
      (node (ref "IC10") (pin "50") (pinfunction "VDD_CORE_50") (pintype "power_in"))
      (node (ref "IC10") (pin "51") (pinfunction "VDD_CORE_51") (pintype "power_in"))
      (node (ref "IC10") (pin "52") (pinfunction "VDD_CORE_52") (pintype "power_in"))
      (node (ref "IC10") (pin "53") (pinfunction "VDD_CORE_53") (pintype "power_in"))
      (node (ref "IC10") (pin "54") (pinfunction "VDD_CORE_54") (pintype "power_in"))
      (node (ref "IC10") (pin "55") (pinfunction "VDD_CORE_55") (pintype "power_in"))
      (node (ref "IC10") (pin "57") (pinfunction "VDD_CORE_57") (pintype "power_in"))
      (node (ref "IC10") (pin "58") (pinfunction "VDD_CORE_58") (pintype "power_in"))
      (node (ref "IC10") (pin "59") (pinfunction "VDD_CORE_59") (pintype "power_in"))
      (node (ref "IC10") (pin "60") (pinfunction "VDD_CORE_60") (pintype "power_in"))
      (node (ref "IC10") (pin "61") (pinfunction "VDD_CORE_61") (pintype "power_in"))
      (node (ref "IC10") (pin "62") (pinfunction "VDD_CORE_62") (pintype "power_in"))
      (node (ref "IC10") (pin "63") (pinfunction "VDD_CORE_63") (pintype "power_in"))
      (node (ref "IC10") (pin "64") (pinfunction "VDD_CORE_64") (pintype "power_in"))
      (node (ref "IC11") (pin "1") (pinfunction "VDD_CORE_1") (pintype "power_in"))
      (node (ref "IC11") (pin "14") (pinfunction "VDD_CORE_14") (pintype "power_in"))
      (node (ref "IC11") (pin "15") (pinfunction "VDD_CORE_15") (pintype "power_in"))
      (node (ref "IC11") (pin "16") (pinfunction "VDD_CORE_16") (pintype "power_in"))
      (node (ref "IC11") (pin "17") (pinfunction "VDD_CORE_17") (pintype "power_in"))
      (node (ref "IC11") (pin "18") (pinfunction "VDD_CORE_18") (pintype "power_in"))
      (node (ref "IC11") (pin "19") (pinfunction "VDD_CORE_19") (pintype "power_in"))
      (node (ref "IC11") (pin "2") (pinfunction "VDD_CORE_2") (pintype "power_in"))
      (node (ref "IC11") (pin "20") (pinfunction "VDD_CORE_20") (pintype "power_in"))
      (node (ref "IC11") (pin "21") (pinfunction "VDD_CORE_21") (pintype "power_in"))
      (node (ref "IC11") (pin "22") (pinfunction "VDD_CORE_22") (pintype "power_in"))
      (node (ref "IC11") (pin "23") (pinfunction "VDD_CORE_23") (pintype "power_in"))
      (node (ref "IC11") (pin "24") (pinfunction "VDD_CORE_24") (pintype "power_in"))
      (node (ref "IC11") (pin "26") (pinfunction "VDD_CORE_26") (pintype "power_in"))
      (node (ref "IC11") (pin "27") (pinfunction "VDD_CORE_27") (pintype "power_in"))
      (node (ref "IC11") (pin "28") (pinfunction "VDD_CORE_28") (pintype "power_in"))
      (node (ref "IC11") (pin "29") (pinfunction "VDD_CORE_29") (pintype "power_in"))
      (node (ref "IC11") (pin "3") (pinfunction "VDD_CORE_3") (pintype "power_in"))
      (node (ref "IC11") (pin "30") (pinfunction "VDD_CORE_30") (pintype "power_in"))
      (node (ref "IC11") (pin "31") (pinfunction "VDD_CORE_31") (pintype "power_in"))
      (node (ref "IC11") (pin "32") (pinfunction "VDD_CORE_32") (pintype "power_in"))
      (node (ref "IC11") (pin "33") (pinfunction "VDD_CORE_33") (pintype "power_in"))
      (node (ref "IC11") (pin "34") (pinfunction "VDD_CORE_34") (pintype "power_in"))
      (node (ref "IC11") (pin "35") (pinfunction "VDD_CORE_35") (pintype "power_in"))
      (node (ref "IC11") (pin "36") (pinfunction "VDD_CORE_36") (pintype "power_in"))
      (node (ref "IC11") (pin "4") (pinfunction "VDD_CORE_4") (pintype "power_in"))
      (node (ref "IC11") (pin "45") (pinfunction "VDD_CORE_45") (pintype "power_in"))
      (node (ref "IC11") (pin "46") (pinfunction "VDD_CORE_46") (pintype "power_in"))
      (node (ref "IC11") (pin "47") (pinfunction "VDD_CORE_47") (pintype "power_in"))
      (node (ref "IC11") (pin "48") (pinfunction "VDD_CORE_48") (pintype "power_in"))
      (node (ref "IC11") (pin "49") (pinfunction "VDD_CORE_49") (pintype "power_in"))
      (node (ref "IC11") (pin "50") (pinfunction "VDD_CORE_50") (pintype "power_in"))
      (node (ref "IC11") (pin "51") (pinfunction "VDD_CORE_51") (pintype "power_in"))
      (node (ref "IC11") (pin "52") (pinfunction "VDD_CORE_52") (pintype "power_in"))
      (node (ref "IC11") (pin "53") (pinfunction "VDD_CORE_53") (pintype "power_in"))
      (node (ref "IC11") (pin "54") (pinfunction "VDD_CORE_54") (pintype "power_in"))
      (node (ref "IC11") (pin "55") (pinfunction "VDD_CORE_55") (pintype "power_in"))
      (node (ref "IC11") (pin "57") (pinfunction "VDD_CORE_57") (pintype "power_in"))
      (node (ref "IC11") (pin "58") (pinfunction "VDD_CORE_58") (pintype "power_in"))
      (node (ref "IC11") (pin "59") (pinfunction "VDD_CORE_59") (pintype "power_in"))
      (node (ref "IC11") (pin "60") (pinfunction "VDD_CORE_60") (pintype "power_in"))
      (node (ref "IC11") (pin "61") (pinfunction "VDD_CORE_61") (pintype "power_in"))
      (node (ref "IC11") (pin "62") (pinfunction "VDD_CORE_62") (pintype "power_in"))
      (node (ref "IC11") (pin "63") (pinfunction "VDD_CORE_63") (pintype "power_in"))
      (node (ref "IC11") (pin "64") (pinfunction "VDD_CORE_64") (pintype "power_in"))
      (node (ref "IC8") (pin "1") (pinfunction "VDD_CORE_1") (pintype "power_in"))
      (node (ref "IC8") (pin "14") (pinfunction "VDD_CORE_14") (pintype "power_in"))
      (node (ref "IC8") (pin "15") (pinfunction "VDD_CORE_15") (pintype "power_in"))
      (node (ref "IC8") (pin "16") (pinfunction "VDD_CORE_16") (pintype "power_in"))
      (node (ref "IC8") (pin "17") (pinfunction "VDD_CORE_17") (pintype "power_in"))
      (node (ref "IC8") (pin "18") (pinfunction "VDD_CORE_18") (pintype "power_in"))
      (node (ref "IC8") (pin "19") (pinfunction "VDD_CORE_19") (pintype "power_in"))
      (node (ref "IC8") (pin "2") (pinfunction "VDD_CORE_2") (pintype "power_in"))
      (node (ref "IC8") (pin "20") (pinfunction "VDD_CORE_20") (pintype "power_in"))
      (node (ref "IC8") (pin "21") (pinfunction "VDD_CORE_21") (pintype "power_in"))
      (node (ref "IC8") (pin "22") (pinfunction "VDD_CORE_22") (pintype "power_in"))
      (node (ref "IC8") (pin "23") (pinfunction "VDD_CORE_23") (pintype "power_in"))
      (node (ref "IC8") (pin "24") (pinfunction "VDD_CORE_24") (pintype "power_in"))
      (node (ref "IC8") (pin "26") (pinfunction "VDD_CORE_26") (pintype "power_in"))
      (node (ref "IC8") (pin "27") (pinfunction "VDD_CORE_27") (pintype "power_in"))
      (node (ref "IC8") (pin "28") (pinfunction "VDD_CORE_28") (pintype "power_in"))
      (node (ref "IC8") (pin "29") (pinfunction "VDD_CORE_29") (pintype "power_in"))
      (node (ref "IC8") (pin "3") (pinfunction "VDD_CORE_3") (pintype "power_in"))
      (node (ref "IC8") (pin "30") (pinfunction "VDD_CORE_30") (pintype "power_in"))
      (node (ref "IC8") (pin "31") (pinfunction "VDD_CORE_31") (pintype "power_in"))
      (node (ref "IC8") (pin "32") (pinfunction "VDD_CORE_32") (pintype "power_in"))
      (node (ref "IC8") (pin "33") (pinfunction "VDD_CORE_33") (pintype "power_in"))
      (node (ref "IC8") (pin "34") (pinfunction "VDD_CORE_34") (pintype "power_in"))
      (node (ref "IC8") (pin "35") (pinfunction "VDD_CORE_35") (pintype "power_in"))
      (node (ref "IC8") (pin "36") (pinfunction "VDD_CORE_36") (pintype "power_in"))
      (node (ref "IC8") (pin "4") (pinfunction "VDD_CORE_4") (pintype "power_in"))
      (node (ref "IC8") (pin "45") (pinfunction "VDD_CORE_45") (pintype "power_in"))
      (node (ref "IC8") (pin "46") (pinfunction "VDD_CORE_46") (pintype "power_in"))
      (node (ref "IC8") (pin "47") (pinfunction "VDD_CORE_47") (pintype "power_in"))
      (node (ref "IC8") (pin "48") (pinfunction "VDD_CORE_48") (pintype "power_in"))
      (node (ref "IC8") (pin "49") (pinfunction "VDD_CORE_49") (pintype "power_in"))
      (node (ref "IC8") (pin "50") (pinfunction "VDD_CORE_50") (pintype "power_in"))
      (node (ref "IC8") (pin "51") (pinfunction "VDD_CORE_51") (pintype "power_in"))
      (node (ref "IC8") (pin "52") (pinfunction "VDD_CORE_52") (pintype "power_in"))
      (node (ref "IC8") (pin "53") (pinfunction "VDD_CORE_53") (pintype "power_in"))
      (node (ref "IC8") (pin "54") (pinfunction "VDD_CORE_54") (pintype "power_in"))
      (node (ref "IC8") (pin "55") (pinfunction "VDD_CORE_55") (pintype "power_in"))
      (node (ref "IC8") (pin "57") (pinfunction "VDD_CORE_57") (pintype "power_in"))
      (node (ref "IC8") (pin "58") (pinfunction "VDD_CORE_58") (pintype "power_in"))
      (node (ref "IC8") (pin "59") (pinfunction "VDD_CORE_59") (pintype "power_in"))
      (node (ref "IC8") (pin "60") (pinfunction "VDD_CORE_60") (pintype "power_in"))
      (node (ref "IC8") (pin "61") (pinfunction "VDD_CORE_61") (pintype "power_in"))
      (node (ref "IC8") (pin "62") (pinfunction "VDD_CORE_62") (pintype "power_in"))
      (node (ref "IC8") (pin "63") (pinfunction "VDD_CORE_63") (pintype "power_in"))
      (node (ref "IC8") (pin "64") (pinfunction "VDD_CORE_64") (pintype "power_in"))
      (node (ref "IC9") (pin "1") (pinfunction "VDD_CORE_1") (pintype "power_in"))
      (node (ref "IC9") (pin "14") (pinfunction "VDD_CORE_14") (pintype "power_in"))
      (node (ref "IC9") (pin "15") (pinfunction "VDD_CORE_15") (pintype "power_in"))
      (node (ref "IC9") (pin "16") (pinfunction "VDD_CORE_16") (pintype "power_in"))
      (node (ref "IC9") (pin "17") (pinfunction "VDD_CORE_17") (pintype "power_in"))
      (node (ref "IC9") (pin "18") (pinfunction "VDD_CORE_18") (pintype "power_in"))
      (node (ref "IC9") (pin "19") (pinfunction "VDD_CORE_19") (pintype "power_in"))
      (node (ref "IC9") (pin "2") (pinfunction "VDD_CORE_2") (pintype "power_in"))
      (node (ref "IC9") (pin "20") (pinfunction "VDD_CORE_20") (pintype "power_in"))
      (node (ref "IC9") (pin "21") (pinfunction "VDD_CORE_21") (pintype "power_in"))
      (node (ref "IC9") (pin "22") (pinfunction "VDD_CORE_22") (pintype "power_in"))
      (node (ref "IC9") (pin "23") (pinfunction "VDD_CORE_23") (pintype "power_in"))
      (node (ref "IC9") (pin "24") (pinfunction "VDD_CORE_24") (pintype "power_in"))
      (node (ref "IC9") (pin "26") (pinfunction "VDD_CORE_26") (pintype "power_in"))
      (node (ref "IC9") (pin "27") (pinfunction "VDD_CORE_27") (pintype "power_in"))
      (node (ref "IC9") (pin "28") (pinfunction "VDD_CORE_28") (pintype "power_in"))
      (node (ref "IC9") (pin "29") (pinfunction "VDD_CORE_29") (pintype "power_in"))
      (node (ref "IC9") (pin "3") (pinfunction "VDD_CORE_3") (pintype "power_in"))
      (node (ref "IC9") (pin "30") (pinfunction "VDD_CORE_30") (pintype "power_in"))
      (node (ref "IC9") (pin "31") (pinfunction "VDD_CORE_31") (pintype "power_in"))
      (node (ref "IC9") (pin "32") (pinfunction "VDD_CORE_32") (pintype "power_in"))
      (node (ref "IC9") (pin "33") (pinfunction "VDD_CORE_33") (pintype "power_in"))
      (node (ref "IC9") (pin "34") (pinfunction "VDD_CORE_34") (pintype "power_in"))
      (node (ref "IC9") (pin "35") (pinfunction "VDD_CORE_35") (pintype "power_in"))
      (node (ref "IC9") (pin "36") (pinfunction "VDD_CORE_36") (pintype "power_in"))
      (node (ref "IC9") (pin "4") (pinfunction "VDD_CORE_4") (pintype "power_in"))
      (node (ref "IC9") (pin "45") (pinfunction "VDD_CORE_45") (pintype "power_in"))
      (node (ref "IC9") (pin "46") (pinfunction "VDD_CORE_46") (pintype "power_in"))
      (node (ref "IC9") (pin "47") (pinfunction "VDD_CORE_47") (pintype "power_in"))
      (node (ref "IC9") (pin "48") (pinfunction "VDD_CORE_48") (pintype "power_in"))
      (node (ref "IC9") (pin "49") (pinfunction "VDD_CORE_49") (pintype "power_in"))
      (node (ref "IC9") (pin "50") (pinfunction "VDD_CORE_50") (pintype "power_in"))
      (node (ref "IC9") (pin "51") (pinfunction "VDD_CORE_51") (pintype "power_in"))
      (node (ref "IC9") (pin "52") (pinfunction "VDD_CORE_52") (pintype "power_in"))
      (node (ref "IC9") (pin "53") (pinfunction "VDD_CORE_53") (pintype "power_in"))
      (node (ref "IC9") (pin "54") (pinfunction "VDD_CORE_54") (pintype "power_in"))
      (node (ref "IC9") (pin "55") (pinfunction "VDD_CORE_55") (pintype "power_in"))
      (node (ref "IC9") (pin "57") (pinfunction "VDD_CORE_57") (pintype "power_in"))
      (node (ref "IC9") (pin "58") (pinfunction "VDD_CORE_58") (pintype "power_in"))
      (node (ref "IC9") (pin "59") (pinfunction "VDD_CORE_59") (pintype "power_in"))
      (node (ref "IC9") (pin "60") (pinfunction "VDD_CORE_60") (pintype "power_in"))
      (node (ref "IC9") (pin "61") (pinfunction "VDD_CORE_61") (pintype "power_in"))
      (node (ref "IC9") (pin "62") (pinfunction "VDD_CORE_62") (pintype "power_in"))
      (node (ref "IC9") (pin "63") (pinfunction "VDD_CORE_63") (pintype "power_in"))
      (node (ref "IC9") (pin "64") (pinfunction "VDD_CORE_64") (pintype "power_in"))
      (node (ref "R15") (pin "2") (pinfunction "2_2") (pintype "passive"))
      (node (ref "R16") (pin "2") (pinfunction "2_2") (pintype "passive"))
      (node (ref "R17") (pin "2") (pinfunction "2_2") (pintype "passive"))
      (node (ref "R18") (pin "2") (pinfunction "2_2") (pintype "passive"))
      (node (ref "R19") (pin "2") (pinfunction "2_2") (pintype "passive"))
      (node (ref "R20") (pin "2") (pinfunction "2_2") (pintype "passive"))
      (node (ref "R21") (pin "2") (pinfunction "2_2") (pintype "passive"))
      (node (ref "R22") (pin "2") (pinfunction "2_2") (pintype "passive"))
      (node (ref "R23") (pin "2") (pinfunction "2_2") (pintype "passive"))
      (node (ref "R24") (pin "2") (pinfunction "2_2") (pintype "passive"))
      (node (ref "R25") (pin "2") (pinfunction "2_2") (pintype "passive"))
      (node (ref "R26") (pin "2") (pinfunction "2_2") (pintype "passive"))
      (node (ref "R27") (pin "2") (pinfunction "2_2") (pintype "passive"))
      (node (ref "R28") (pin "2") (pinfunction "2_2") (pintype "passive"))
      (node (ref "R29") (pin "2") (pinfunction "2_2") (pintype "passive"))
      (node (ref "R30") (pin "2") (pinfunction "2_2") (pintype "passive"))
      (node (ref "TP5") (pin "1") (pinfunction "1_1") (pintype "passive"))
    )
    (net (code "34") (name "/VDD_IO") (class "Default")
      (node (ref "C36") (pin "1") (pinfunction "1_1") (pintype "passive"))
      (node (ref "C39") (pin "1") (pinfunction "1_1") (pintype "passive"))
      (node (ref "C42") (pin "1") (pinfunction "1_1") (pintype "passive"))
      (node (ref "C45") (pin "1") (pinfunction "1_1") (pintype "passive"))
      (node (ref "IC10") (pin "25") (pinfunction "VDD_IO_25") (pintype "power_in"))
      (node (ref "IC10") (pin "37") (pinfunction "VDD_IO_37") (pintype "power_in"))
      (node (ref "IC10") (pin "5") (pinfunction "PLLIOVDD_5") (pintype "power_in"))
      (node (ref "IC10") (pin "56") (pinfunction "VDD_IO_56") (pintype "power_in"))
      (node (ref "IC11") (pin "25") (pinfunction "VDD_IO_25") (pintype "power_in"))
      (node (ref "IC11") (pin "37") (pinfunction "VDD_IO_37") (pintype "power_in"))
      (node (ref "IC11") (pin "5") (pinfunction "PLLIOVDD_5") (pintype "power_in"))
      (node (ref "IC11") (pin "56") (pinfunction "VDD_IO_56") (pintype "power_in"))
      (node (ref "IC8") (pin "25") (pinfunction "VDD_IO_25") (pintype "power_in"))
      (node (ref "IC8") (pin "37") (pinfunction "VDD_IO_37") (pintype "power_in"))
      (node (ref "IC8") (pin "5") (pinfunction "PLLIOVDD_5") (pintype "power_in"))
      (node (ref "IC8") (pin "56") (pinfunction "VDD_IO_56") (pintype "power_in"))
      (node (ref "IC9") (pin "25") (pinfunction "VDD_IO_25") (pintype "power_in"))
      (node (ref "IC9") (pin "37") (pinfunction "VDD_IO_37") (pintype "power_in"))
      (node (ref "IC9") (pin "5") (pinfunction "PLLIOVDD_5") (pintype "power_in"))
      (node (ref "IC9") (pin "56") (pinfunction "VDD_IO_56") (pintype "power_in"))
      (node (ref "JP2") (pin "2") (pinfunction "2_2") (pintype "passive"))
    )
    (net (code "35") (name "/VFB") (class "Default")
      (node (ref "C8") (pin "2") (pinfunction "2_2") (pintype "passive"))
      (node (ref "IC1") (pin "1") (pinfunction "VFB_1") (pintype "output"))
      (node (ref "R5") (pin "2") (pinfunction "2_2") (pintype "passive"))
      (node (ref "R6") (pin "A") (pinfunction "A_A") (pintype "passive"))
    )
    (net (code "36") (name "/{slash}CS_EN") (class "Default")
      (node (ref "IC12") (pin "4") (pinfunction "G2A_4") (pintype "input"))
      (node (ref "IC12") (pin "5") (pinfunction "G2B_5") (pintype "input"))
      (node (ref "IC6") (pin "14") (pinfunction "PB2(SS/OC1B/PCINT2)_14") (pintype "bidirectional"))
      (node (ref "R31") (pin "1") (pinfunction "1_1") (pintype "passive"))
    )
    (net (code "37") (name "GND") (class "Default")
      (node (ref "C1") (pin "-") (pinfunction "-_-") (pintype "passive"))
      (node (ref "C11") (pin "2") (pinfunction "2_2") (pintype "passive"))
      (node (ref "C12") (pin "2") (pinfunction "2_2") (pintype "passive"))
      (node (ref "C13") (pin "2") (pinfunction "2_2") (pintype "passive"))
      (node (ref "C14") (pin "2") (pinfunction "2_2") (pintype "passive"))
      (node (ref "C15") (pin "2") (pinfunction "2_2") (pintype "passive"))
      (node (ref "C16") (pin "2") (pinfunction "2_2") (pintype "passive"))
      (node (ref "C17") (pin "2") (pinfunction "2_2") (pintype "passive"))
      (node (ref "C18") (pin "2") (pinfunction "2_2") (pintype "passive"))
      (node (ref "C19") (pin "2") (pinfunction "2_2") (pintype "passive"))
      (node (ref "C2") (pin "2") (pinfunction "2_2") (pintype "passive"))
      (node (ref "C20") (pin "2") (pinfunction "2_2") (pintype "passive"))
      (node (ref "C21") (pin "1") (pinfunction "1_1") (pintype "passive"))
      (node (ref "C22") (pin "1") (pinfunction "1_1") (pintype "passive"))
      (node (ref "C23") (pin "1") (pinfunction "1_1") (pintype "passive"))
      (node (ref "C24") (pin "1") (pinfunction "1_1") (pintype "passive"))
      (node (ref "C25") (pin "1") (pinfunction "1_1") (pintype "passive"))
      (node (ref "C26") (pin "1") (pinfunction "1_1") (pintype "passive"))
      (node (ref "C27") (pin "1") (pinfunction "1_1") (pintype "passive"))
      (node (ref "C28") (pin "1") (pinfunction "1_1") (pintype "passive"))
      (node (ref "C29") (pin "1") (pinfunction "1_1") (pintype "passive"))
      (node (ref "C3") (pin "2") (pinfunction "2_2") (pintype "passive"))
      (node (ref "C30") (pin "1") (pinfunction "1_1") (pintype "passive"))
      (node (ref "C31") (pin "2") (pinfunction "2_2") (pintype "passive"))
      (node (ref "C32") (pin "2") (pinfunction "2_2") (pintype "passive"))
      (node (ref "C33") (pin "1") (pinfunction "1_1") (pintype "passive"))
      (node (ref "C34") (pin "1") (pinfunction "1_1") (pintype "passive"))
      (node (ref "C35") (pin "2") (pinfunction "2_2") (pintype "passive"))
      (node (ref "C36") (pin "2") (pinfunction "2_2") (pintype "passive"))
      (node (ref "C37") (pin "1") (pinfunction "1_1") (pintype "passive"))
      (node (ref "C38") (pin "2") (pinfunction "2_2") (pintype "passive"))
      (node (ref "C39") (pin "2") (pinfunction "2_2") (pintype "passive"))
      (node (ref "C4") (pin "2") (pinfunction "2_2") (pintype "passive"))
      (node (ref "C40") (pin "1") (pinfunction "1_1") (pintype "passive"))
      (node (ref "C41") (pin "2") (pinfunction "2_2") (pintype "passive"))
      (node (ref "C42") (pin "2") (pinfunction "2_2") (pintype "passive"))
      (node (ref "C43") (pin "1") (pinfunction "1_1") (pintype "passive"))
      (node (ref "C44") (pin "2") (pinfunction "2_2") (pintype "passive"))
      (node (ref "C45") (pin "2") (pinfunction "2_2") (pintype "passive"))
      (node (ref "C46") (pin "2") (pinfunction "2_2") (pintype "passive"))
      (node (ref "C47") (pin "2") (pinfunction "2_2") (pintype "passive"))
      (node (ref "C48") (pin "2") (pinfunction "2_2") (pintype "passive"))
      (node (ref "C49") (pin "2") (pinfunction "2_2") (pintype "passive"))
      (node (ref "C5") (pin "2") (pinfunction "2_2") (pintype "passive"))
      (node (ref "C50") (pin "2") (pinfunction "2_2") (pintype "passive"))
      (node (ref "C51") (pin "2") (pinfunction "2_2") (pintype "passive"))
      (node (ref "C52") (pin "2") (pinfunction "2_2") (pintype "passive"))
      (node (ref "C53") (pin "2") (pinfunction "2_2") (pintype "passive"))
      (node (ref "C54") (pin "2") (pinfunction "2_2") (pintype "passive"))
      (node (ref "C55") (pin "2") (pinfunction "2_2") (pintype "passive"))
      (node (ref "C56") (pin "2") (pinfunction "2_2") (pintype "passive"))
      (node (ref "C57") (pin "2") (pinfunction "2_2") (pintype "passive"))
      (node (ref "C58") (pin "2") (pinfunction "2_2") (pintype "passive"))
      (node (ref "C59") (pin "2") (pinfunction "2_2") (pintype "passive"))
      (node (ref "C6") (pin "2") (pinfunction "2_2") (pintype "passive"))
      (node (ref "C60") (pin "2") (pinfunction "2_2") (pintype "passive"))
      (node (ref "C61") (pin "2") (pinfunction "2_2") (pintype "passive"))
      (node (ref "C7") (pin "2") (pinfunction "2_2") (pintype "passive"))
      (node (ref "D1") (pin "A") (pinfunction "A_A") (pintype "passive"))
      (node (ref "IC1") (pin "23") (pinfunction "EPAD_23") (pintype "passive"))
      (node (ref "IC1") (pin "GND@1") (pinfunction "GND_GND@1") (pintype "power_in"))
      (node (ref "IC1") (pin "GND@10") (pinfunction "GND_GND@10") (pintype "power_in"))
      (node (ref "IC1") (pin "GND@11") (pinfunction "GND_GND@11") (pintype "power_in"))
      (node (ref "IC1") (pin "GND@12") (pinfunction "GND_GND@12") (pintype "power_in"))
      (node (ref "IC1") (pin "GND@13") (pinfunction "GND_GND@13") (pintype "power_in"))
      (node (ref "IC1") (pin "GND@14") (pinfunction "GND_GND@14") (pintype "power_in"))
      (node (ref "IC1") (pin "GND@15") (pinfunction "GND_GND@15") (pintype "power_in"))
      (node (ref "IC1") (pin "GND@16") (pinfunction "GND_GND@16") (pintype "power_in"))
      (node (ref "IC1") (pin "GND@17") (pinfunction "GND_GND@17") (pintype "power_in"))
      (node (ref "IC1") (pin "GND@18") (pinfunction "GND_GND@18") (pintype "power_in"))
      (node (ref "IC1") (pin "GND@19") (pinfunction "GND_GND@19") (pintype "power_in"))
      (node (ref "IC1") (pin "GND@2") (pinfunction "GND_GND@2") (pintype "power_in"))
      (node (ref "IC1") (pin "GND@20") (pinfunction "GND_GND@20") (pintype "power_in"))
      (node (ref "IC1") (pin "GND@21") (pinfunction "GND_GND@21") (pintype "power_in"))
      (node (ref "IC1") (pin "GND@22") (pinfunction "GND_GND@22") (pintype "power_in"))
      (node (ref "IC1") (pin "GND@23") (pinfunction "GND_GND@23") (pintype "power_in"))
      (node (ref "IC1") (pin "GND@24") (pinfunction "GND_GND@24") (pintype "power_in"))
      (node (ref "IC1") (pin "GND@3") (pinfunction "GND_GND@3") (pintype "power_in"))
      (node (ref "IC1") (pin "GND@4") (pinfunction "GND_GND@4") (pintype "power_in"))
      (node (ref "IC1") (pin "GND@5") (pinfunction "GND_GND@5") (pintype "power_in"))
      (node (ref "IC1") (pin "GND@6") (pinfunction "GND_GND@6") (pintype "power_in"))
      (node (ref "IC1") (pin "GND@7") (pinfunction "GND_GND@7") (pintype "power_in"))
      (node (ref "IC1") (pin "GND@8") (pinfunction "GND_GND@8") (pintype "power_in"))
      (node (ref "IC1") (pin "GND@9") (pinfunction "GND_GND@9") (pintype "power_in"))
      (node (ref "IC10") (pin "11") (pinfunction "PLLVSS_11") (pintype "power_in"))
      (node (ref "IC10") (pin "7") (pinfunction "PLLAHVSS_7") (pintype "power_in"))
      (node (ref "IC10") (pin "9") (pinfunction "PLLDVSS_9") (pintype "power_in"))
      (node (ref "IC10") (pin "EXP@1") (pinfunction "GND_EXP@1") (pintype "power_in"))
      (node (ref "IC10") (pin "EXP@10") (pinfunction "GND_EXP@10") (pintype "power_in"))
      (node (ref "IC10") (pin "EXP@11") (pinfunction "GND_EXP@11") (pintype "power_in"))
      (node (ref "IC10") (pin "EXP@12") (pinfunction "GND_EXP@12") (pintype "power_in"))
      (node (ref "IC10") (pin "EXP@13") (pinfunction "GND_EXP@13") (pintype "power_in"))
      (node (ref "IC10") (pin "EXP@14") (pinfunction "GND_EXP@14") (pintype "power_in"))
      (node (ref "IC10") (pin "EXP@15") (pinfunction "GND_EXP@15") (pintype "power_in"))
      (node (ref "IC10") (pin "EXP@16") (pinfunction "GND_EXP@16") (pintype "power_in"))
      (node (ref "IC10") (pin "EXP@17") (pinfunction "GND_EXP@17") (pintype "power_in"))
      (node (ref "IC10") (pin "EXP@18") (pinfunction "GND_EXP@18") (pintype "power_in"))
      (node (ref "IC10") (pin "EXP@19") (pinfunction "GND_EXP@19") (pintype "power_in"))
      (node (ref "IC10") (pin "EXP@2") (pinfunction "GND_EXP@2") (pintype "power_in"))
      (node (ref "IC10") (pin "EXP@20") (pinfunction "GND_EXP@20") (pintype "power_in"))
      (node (ref "IC10") (pin "EXP@21") (pinfunction "GND_EXP@21") (pintype "power_in"))
      (node (ref "IC10") (pin "EXP@22") (pinfunction "GND_EXP@22") (pintype "power_in"))
      (node (ref "IC10") (pin "EXP@23") (pinfunction "GND_EXP@23") (pintype "power_in"))
      (node (ref "IC10") (pin "EXP@24") (pinfunction "GND_EXP@24") (pintype "power_in"))
      (node (ref "IC10") (pin "EXP@25") (pinfunction "GND_EXP@25") (pintype "power_in"))
      (node (ref "IC10") (pin "EXP@26") (pinfunction "GND_EXP@26") (pintype "power_in"))
      (node (ref "IC10") (pin "EXP@27") (pinfunction "GND_EXP@27") (pintype "power_in"))
      (node (ref "IC10") (pin "EXP@28") (pinfunction "GND_EXP@28") (pintype "power_in"))
      (node (ref "IC10") (pin "EXP@29") (pinfunction "GND_EXP@29") (pintype "power_in"))
      (node (ref "IC10") (pin "EXP@3") (pinfunction "GND_EXP@3") (pintype "power_in"))
      (node (ref "IC10") (pin "EXP@30") (pinfunction "GND_EXP@30") (pintype "power_in"))
      (node (ref "IC10") (pin "EXP@31") (pinfunction "GND_EXP@31") (pintype "power_in"))
      (node (ref "IC10") (pin "EXP@32") (pinfunction "GND_EXP@32") (pintype "power_in"))
      (node (ref "IC10") (pin "EXP@33") (pinfunction "GND_EXP@33") (pintype "power_in"))
      (node (ref "IC10") (pin "EXP@34") (pinfunction "GND_EXP@34") (pintype "power_in"))
      (node (ref "IC10") (pin "EXP@35") (pinfunction "GND_EXP@35") (pintype "power_in"))
      (node (ref "IC10") (pin "EXP@36") (pinfunction "GND_EXP@36") (pintype "power_in"))
      (node (ref "IC10") (pin "EXP@37") (pinfunction "GND_EXP@37") (pintype "power_in"))
      (node (ref "IC10") (pin "EXP@38") (pinfunction "GND_EXP@38") (pintype "power_in"))
      (node (ref "IC10") (pin "EXP@39") (pinfunction "GND_EXP@39") (pintype "power_in"))
      (node (ref "IC10") (pin "EXP@4") (pinfunction "GND_EXP@4") (pintype "power_in"))
      (node (ref "IC10") (pin "EXP@40") (pinfunction "GND_EXP@40") (pintype "power_in"))
      (node (ref "IC10") (pin "EXP@41") (pinfunction "GND_EXP@41") (pintype "power_in"))
      (node (ref "IC10") (pin "EXP@42") (pinfunction "GND_EXP@42") (pintype "power_in"))
      (node (ref "IC10") (pin "EXP@43") (pinfunction "GND_EXP@43") (pintype "power_in"))
      (node (ref "IC10") (pin "EXP@44") (pinfunction "GND_EXP@44") (pintype "power_in"))
      (node (ref "IC10") (pin "EXP@45") (pinfunction "GND_EXP@45") (pintype "power_in"))
      (node (ref "IC10") (pin "EXP@46") (pinfunction "GND_EXP@46") (pintype "power_in"))
      (node (ref "IC10") (pin "EXP@47") (pinfunction "GND_EXP@47") (pintype "power_in"))
      (node (ref "IC10") (pin "EXP@48") (pinfunction "GND_EXP@48") (pintype "power_in"))
      (node (ref "IC10") (pin "EXP@49") (pinfunction "GND_EXP@49") (pintype "power_in"))
      (node (ref "IC10") (pin "EXP@5") (pinfunction "GND_EXP@5") (pintype "power_in"))
      (node (ref "IC10") (pin "EXP@6") (pinfunction "GND_EXP@6") (pintype "power_in"))
      (node (ref "IC10") (pin "EXP@7") (pinfunction "GND_EXP@7") (pintype "power_in"))
      (node (ref "IC10") (pin "EXP@8") (pinfunction "GND_EXP@8") (pintype "power_in"))
      (node (ref "IC10") (pin "EXP@9") (pinfunction "GND_EXP@9") (pintype "power_in"))
      (node (ref "IC11") (pin "11") (pinfunction "PLLVSS_11") (pintype "power_in"))
      (node (ref "IC11") (pin "7") (pinfunction "PLLAHVSS_7") (pintype "power_in"))
      (node (ref "IC11") (pin "9") (pinfunction "PLLDVSS_9") (pintype "power_in"))
      (node (ref "IC11") (pin "EXP@1") (pinfunction "GND_EXP@1") (pintype "power_in"))
      (node (ref "IC11") (pin "EXP@10") (pinfunction "GND_EXP@10") (pintype "power_in"))
      (node (ref "IC11") (pin "EXP@11") (pinfunction "GND_EXP@11") (pintype "power_in"))
      (node (ref "IC11") (pin "EXP@12") (pinfunction "GND_EXP@12") (pintype "power_in"))
      (node (ref "IC11") (pin "EXP@13") (pinfunction "GND_EXP@13") (pintype "power_in"))
      (node (ref "IC11") (pin "EXP@14") (pinfunction "GND_EXP@14") (pintype "power_in"))
      (node (ref "IC11") (pin "EXP@15") (pinfunction "GND_EXP@15") (pintype "power_in"))
      (node (ref "IC11") (pin "EXP@16") (pinfunction "GND_EXP@16") (pintype "power_in"))
      (node (ref "IC11") (pin "EXP@17") (pinfunction "GND_EXP@17") (pintype "power_in"))
      (node (ref "IC11") (pin "EXP@18") (pinfunction "GND_EXP@18") (pintype "power_in"))
      (node (ref "IC11") (pin "EXP@19") (pinfunction "GND_EXP@19") (pintype "power_in"))
      (node (ref "IC11") (pin "EXP@2") (pinfunction "GND_EXP@2") (pintype "power_in"))
      (node (ref "IC11") (pin "EXP@20") (pinfunction "GND_EXP@20") (pintype "power_in"))
      (node (ref "IC11") (pin "EXP@21") (pinfunction "GND_EXP@21") (pintype "power_in"))
      (node (ref "IC11") (pin "EXP@22") (pinfunction "GND_EXP@22") (pintype "power_in"))
      (node (ref "IC11") (pin "EXP@23") (pinfunction "GND_EXP@23") (pintype "power_in"))
      (node (ref "IC11") (pin "EXP@24") (pinfunction "GND_EXP@24") (pintype "power_in"))
      (node (ref "IC11") (pin "EXP@25") (pinfunction "GND_EXP@25") (pintype "power_in"))
      (node (ref "IC11") (pin "EXP@26") (pinfunction "GND_EXP@26") (pintype "power_in"))
      (node (ref "IC11") (pin "EXP@27") (pinfunction "GND_EXP@27") (pintype "power_in"))
      (node (ref "IC11") (pin "EXP@28") (pinfunction "GND_EXP@28") (pintype "power_in"))
      (node (ref "IC11") (pin "EXP@29") (pinfunction "GND_EXP@29") (pintype "power_in"))
      (node (ref "IC11") (pin "EXP@3") (pinfunction "GND_EXP@3") (pintype "power_in"))
      (node (ref "IC11") (pin "EXP@30") (pinfunction "GND_EXP@30") (pintype "power_in"))
      (node (ref "IC11") (pin "EXP@31") (pinfunction "GND_EXP@31") (pintype "power_in"))
      (node (ref "IC11") (pin "EXP@32") (pinfunction "GND_EXP@32") (pintype "power_in"))
      (node (ref "IC11") (pin "EXP@33") (pinfunction "GND_EXP@33") (pintype "power_in"))
      (node (ref "IC11") (pin "EXP@34") (pinfunction "GND_EXP@34") (pintype "power_in"))
      (node (ref "IC11") (pin "EXP@35") (pinfunction "GND_EXP@35") (pintype "power_in"))
      (node (ref "IC11") (pin "EXP@36") (pinfunction "GND_EXP@36") (pintype "power_in"))
      (node (ref "IC11") (pin "EXP@37") (pinfunction "GND_EXP@37") (pintype "power_in"))
      (node (ref "IC11") (pin "EXP@38") (pinfunction "GND_EXP@38") (pintype "power_in"))
      (node (ref "IC11") (pin "EXP@39") (pinfunction "GND_EXP@39") (pintype "power_in"))
      (node (ref "IC11") (pin "EXP@4") (pinfunction "GND_EXP@4") (pintype "power_in"))
      (node (ref "IC11") (pin "EXP@40") (pinfunction "GND_EXP@40") (pintype "power_in"))
      (node (ref "IC11") (pin "EXP@41") (pinfunction "GND_EXP@41") (pintype "power_in"))
      (node (ref "IC11") (pin "EXP@42") (pinfunction "GND_EXP@42") (pintype "power_in"))
      (node (ref "IC11") (pin "EXP@43") (pinfunction "GND_EXP@43") (pintype "power_in"))
      (node (ref "IC11") (pin "EXP@44") (pinfunction "GND_EXP@44") (pintype "power_in"))
      (node (ref "IC11") (pin "EXP@45") (pinfunction "GND_EXP@45") (pintype "power_in"))
      (node (ref "IC11") (pin "EXP@46") (pinfunction "GND_EXP@46") (pintype "power_in"))
      (node (ref "IC11") (pin "EXP@47") (pinfunction "GND_EXP@47") (pintype "power_in"))
      (node (ref "IC11") (pin "EXP@48") (pinfunction "GND_EXP@48") (pintype "power_in"))
      (node (ref "IC11") (pin "EXP@49") (pinfunction "GND_EXP@49") (pintype "power_in"))
      (node (ref "IC11") (pin "EXP@5") (pinfunction "GND_EXP@5") (pintype "power_in"))
      (node (ref "IC11") (pin "EXP@6") (pinfunction "GND_EXP@6") (pintype "power_in"))
      (node (ref "IC11") (pin "EXP@7") (pinfunction "GND_EXP@7") (pintype "power_in"))
      (node (ref "IC11") (pin "EXP@8") (pinfunction "GND_EXP@8") (pintype "power_in"))
      (node (ref "IC11") (pin "EXP@9") (pinfunction "GND_EXP@9") (pintype "power_in"))
      (node (ref "IC12") (pin "8") (pinfunction "GND_8") (pintype "power_in"))
      (node (ref "IC2") (pin "AGND") (pinfunction "AGND_AGND") (pintype "bidirectional"))
      (node (ref "IC2") (pin "PGND") (pinfunction "PGND_PGND") (pintype "bidirectional"))
      (node (ref "IC3") (pin "2") (pinfunction "GND_2") (pintype "bidirectional"))
      (node (ref "IC4") (pin "2") (pinfunction "GND_2") (pintype "bidirectional"))
      (node (ref "IC5") (pin "3") (pinfunction "GND_3") (pintype "power_in"))
      (node (ref "IC5") (pin "EXP") (pinfunction "GND_EXP") (pintype "power_in"))
      (node (ref "IC5") (pin "M") (pinfunction "GND_M") (pintype "power_in"))
      (node (ref "IC6") (pin "21") (pinfunction "AGND_21") (pintype "power_in"))
      (node (ref "IC6") (pin "3") (pinfunction "GND_3") (pintype "power_in"))
      (node (ref "IC6") (pin "5") (pinfunction "GND_5") (pintype "power_in"))
      (node (ref "IC8") (pin "11") (pinfunction "PLLVSS_11") (pintype "power_in"))
      (node (ref "IC8") (pin "7") (pinfunction "PLLAHVSS_7") (pintype "power_in"))
      (node (ref "IC8") (pin "9") (pinfunction "PLLDVSS_9") (pintype "power_in"))
      (node (ref "IC8") (pin "EXP@1") (pinfunction "GND_EXP@1") (pintype "power_in"))
      (node (ref "IC8") (pin "EXP@10") (pinfunction "GND_EXP@10") (pintype "power_in"))
      (node (ref "IC8") (pin "EXP@11") (pinfunction "GND_EXP@11") (pintype "power_in"))
      (node (ref "IC8") (pin "EXP@12") (pinfunction "GND_EXP@12") (pintype "power_in"))
      (node (ref "IC8") (pin "EXP@13") (pinfunction "GND_EXP@13") (pintype "power_in"))
      (node (ref "IC8") (pin "EXP@14") (pinfunction "GND_EXP@14") (pintype "power_in"))
      (node (ref "IC8") (pin "EXP@15") (pinfunction "GND_EXP@15") (pintype "power_in"))
      (node (ref "IC8") (pin "EXP@16") (pinfunction "GND_EXP@16") (pintype "power_in"))
      (node (ref "IC8") (pin "EXP@17") (pinfunction "GND_EXP@17") (pintype "power_in"))
      (node (ref "IC8") (pin "EXP@18") (pinfunction "GND_EXP@18") (pintype "power_in"))
      (node (ref "IC8") (pin "EXP@19") (pinfunction "GND_EXP@19") (pintype "power_in"))
      (node (ref "IC8") (pin "EXP@2") (pinfunction "GND_EXP@2") (pintype "power_in"))
      (node (ref "IC8") (pin "EXP@20") (pinfunction "GND_EXP@20") (pintype "power_in"))
      (node (ref "IC8") (pin "EXP@21") (pinfunction "GND_EXP@21") (pintype "power_in"))
      (node (ref "IC8") (pin "EXP@22") (pinfunction "GND_EXP@22") (pintype "power_in"))
      (node (ref "IC8") (pin "EXP@23") (pinfunction "GND_EXP@23") (pintype "power_in"))
      (node (ref "IC8") (pin "EXP@24") (pinfunction "GND_EXP@24") (pintype "power_in"))
      (node (ref "IC8") (pin "EXP@25") (pinfunction "GND_EXP@25") (pintype "power_in"))
      (node (ref "IC8") (pin "EXP@26") (pinfunction "GND_EXP@26") (pintype "power_in"))
      (node (ref "IC8") (pin "EXP@27") (pinfunction "GND_EXP@27") (pintype "power_in"))
      (node (ref "IC8") (pin "EXP@28") (pinfunction "GND_EXP@28") (pintype "power_in"))
      (node (ref "IC8") (pin "EXP@29") (pinfunction "GND_EXP@29") (pintype "power_in"))
      (node (ref "IC8") (pin "EXP@3") (pinfunction "GND_EXP@3") (pintype "power_in"))
      (node (ref "IC8") (pin "EXP@30") (pinfunction "GND_EXP@30") (pintype "power_in"))
      (node (ref "IC8") (pin "EXP@31") (pinfunction "GND_EXP@31") (pintype "power_in"))
      (node (ref "IC8") (pin "EXP@32") (pinfunction "GND_EXP@32") (pintype "power_in"))
      (node (ref "IC8") (pin "EXP@33") (pinfunction "GND_EXP@33") (pintype "power_in"))
      (node (ref "IC8") (pin "EXP@34") (pinfunction "GND_EXP@34") (pintype "power_in"))
      (node (ref "IC8") (pin "EXP@35") (pinfunction "GND_EXP@35") (pintype "power_in"))
      (node (ref "IC8") (pin "EXP@36") (pinfunction "GND_EXP@36") (pintype "power_in"))
      (node (ref "IC8") (pin "EXP@37") (pinfunction "GND_EXP@37") (pintype "power_in"))
      (node (ref "IC8") (pin "EXP@38") (pinfunction "GND_EXP@38") (pintype "power_in"))
      (node (ref "IC8") (pin "EXP@39") (pinfunction "GND_EXP@39") (pintype "power_in"))
      (node (ref "IC8") (pin "EXP@4") (pinfunction "GND_EXP@4") (pintype "power_in"))
      (node (ref "IC8") (pin "EXP@40") (pinfunction "GND_EXP@40") (pintype "power_in"))
      (node (ref "IC8") (pin "EXP@41") (pinfunction "GND_EXP@41") (pintype "power_in"))
      (node (ref "IC8") (pin "EXP@42") (pinfunction "GND_EXP@42") (pintype "power_in"))
      (node (ref "IC8") (pin "EXP@43") (pinfunction "GND_EXP@43") (pintype "power_in"))
      (node (ref "IC8") (pin "EXP@44") (pinfunction "GND_EXP@44") (pintype "power_in"))
      (node (ref "IC8") (pin "EXP@45") (pinfunction "GND_EXP@45") (pintype "power_in"))
      (node (ref "IC8") (pin "EXP@46") (pinfunction "GND_EXP@46") (pintype "power_in"))
      (node (ref "IC8") (pin "EXP@47") (pinfunction "GND_EXP@47") (pintype "power_in"))
      (node (ref "IC8") (pin "EXP@48") (pinfunction "GND_EXP@48") (pintype "power_in"))
      (node (ref "IC8") (pin "EXP@49") (pinfunction "GND_EXP@49") (pintype "power_in"))
      (node (ref "IC8") (pin "EXP@5") (pinfunction "GND_EXP@5") (pintype "power_in"))
      (node (ref "IC8") (pin "EXP@6") (pinfunction "GND_EXP@6") (pintype "power_in"))
      (node (ref "IC8") (pin "EXP@7") (pinfunction "GND_EXP@7") (pintype "power_in"))
      (node (ref "IC8") (pin "EXP@8") (pinfunction "GND_EXP@8") (pintype "power_in"))
      (node (ref "IC8") (pin "EXP@9") (pinfunction "GND_EXP@9") (pintype "power_in"))
      (node (ref "IC9") (pin "11") (pinfunction "PLLVSS_11") (pintype "power_in"))
      (node (ref "IC9") (pin "7") (pinfunction "PLLAHVSS_7") (pintype "power_in"))
      (node (ref "IC9") (pin "9") (pinfunction "PLLDVSS_9") (pintype "power_in"))
      (node (ref "IC9") (pin "EXP@1") (pinfunction "GND_EXP@1") (pintype "power_in"))
      (node (ref "IC9") (pin "EXP@10") (pinfunction "GND_EXP@10") (pintype "power_in"))
      (node (ref "IC9") (pin "EXP@11") (pinfunction "GND_EXP@11") (pintype "power_in"))
      (node (ref "IC9") (pin "EXP@12") (pinfunction "GND_EXP@12") (pintype "power_in"))
      (node (ref "IC9") (pin "EXP@13") (pinfunction "GND_EXP@13") (pintype "power_in"))
      (node (ref "IC9") (pin "EXP@14") (pinfunction "GND_EXP@14") (pintype "power_in"))
      (node (ref "IC9") (pin "EXP@15") (pinfunction "GND_EXP@15") (pintype "power_in"))
      (node (ref "IC9") (pin "EXP@16") (pinfunction "GND_EXP@16") (pintype "power_in"))
      (node (ref "IC9") (pin "EXP@17") (pinfunction "GND_EXP@17") (pintype "power_in"))
      (node (ref "IC9") (pin "EXP@18") (pinfunction "GND_EXP@18") (pintype "power_in"))
      (node (ref "IC9") (pin "EXP@19") (pinfunction "GND_EXP@19") (pintype "power_in"))
      (node (ref "IC9") (pin "EXP@2") (pinfunction "GND_EXP@2") (pintype "power_in"))
      (node (ref "IC9") (pin "EXP@20") (pinfunction "GND_EXP@20") (pintype "power_in"))
      (node (ref "IC9") (pin "EXP@21") (pinfunction "GND_EXP@21") (pintype "power_in"))
      (node (ref "IC9") (pin "EXP@22") (pinfunction "GND_EXP@22") (pintype "power_in"))
      (node (ref "IC9") (pin "EXP@23") (pinfunction "GND_EXP@23") (pintype "power_in"))
      (node (ref "IC9") (pin "EXP@24") (pinfunction "GND_EXP@24") (pintype "power_in"))
      (node (ref "IC9") (pin "EXP@25") (pinfunction "GND_EXP@25") (pintype "power_in"))
      (node (ref "IC9") (pin "EXP@26") (pinfunction "GND_EXP@26") (pintype "power_in"))
      (node (ref "IC9") (pin "EXP@27") (pinfunction "GND_EXP@27") (pintype "power_in"))
      (node (ref "IC9") (pin "EXP@28") (pinfunction "GND_EXP@28") (pintype "power_in"))
      (node (ref "IC9") (pin "EXP@29") (pinfunction "GND_EXP@29") (pintype "power_in"))
      (node (ref "IC9") (pin "EXP@3") (pinfunction "GND_EXP@3") (pintype "power_in"))
      (node (ref "IC9") (pin "EXP@30") (pinfunction "GND_EXP@30") (pintype "power_in"))
      (node (ref "IC9") (pin "EXP@31") (pinfunction "GND_EXP@31") (pintype "power_in"))
      (node (ref "IC9") (pin "EXP@32") (pinfunction "GND_EXP@32") (pintype "power_in"))
      (node (ref "IC9") (pin "EXP@33") (pinfunction "GND_EXP@33") (pintype "power_in"))
      (node (ref "IC9") (pin "EXP@34") (pinfunction "GND_EXP@34") (pintype "power_in"))
      (node (ref "IC9") (pin "EXP@35") (pinfunction "GND_EXP@35") (pintype "power_in"))
      (node (ref "IC9") (pin "EXP@36") (pinfunction "GND_EXP@36") (pintype "power_in"))
      (node (ref "IC9") (pin "EXP@37") (pinfunction "GND_EXP@37") (pintype "power_in"))
      (node (ref "IC9") (pin "EXP@38") (pinfunction "GND_EXP@38") (pintype "power_in"))
      (node (ref "IC9") (pin "EXP@39") (pinfunction "GND_EXP@39") (pintype "power_in"))
      (node (ref "IC9") (pin "EXP@4") (pinfunction "GND_EXP@4") (pintype "power_in"))
      (node (ref "IC9") (pin "EXP@40") (pinfunction "GND_EXP@40") (pintype "power_in"))
      (node (ref "IC9") (pin "EXP@41") (pinfunction "GND_EXP@41") (pintype "power_in"))
      (node (ref "IC9") (pin "EXP@42") (pinfunction "GND_EXP@42") (pintype "power_in"))
      (node (ref "IC9") (pin "EXP@43") (pinfunction "GND_EXP@43") (pintype "power_in"))
      (node (ref "IC9") (pin "EXP@44") (pinfunction "GND_EXP@44") (pintype "power_in"))
      (node (ref "IC9") (pin "EXP@45") (pinfunction "GND_EXP@45") (pintype "power_in"))
      (node (ref "IC9") (pin "EXP@46") (pinfunction "GND_EXP@46") (pintype "power_in"))
      (node (ref "IC9") (pin "EXP@47") (pinfunction "GND_EXP@47") (pintype "power_in"))
      (node (ref "IC9") (pin "EXP@48") (pinfunction "GND_EXP@48") (pintype "power_in"))
      (node (ref "IC9") (pin "EXP@49") (pinfunction "GND_EXP@49") (pintype "power_in"))
      (node (ref "IC9") (pin "EXP@5") (pinfunction "GND_EXP@5") (pintype "power_in"))
      (node (ref "IC9") (pin "EXP@6") (pinfunction "GND_EXP@6") (pintype "power_in"))
      (node (ref "IC9") (pin "EXP@7") (pinfunction "GND_EXP@7") (pintype "power_in"))
      (node (ref "IC9") (pin "EXP@8") (pinfunction "GND_EXP@8") (pintype "power_in"))
      (node (ref "IC9") (pin "EXP@9") (pinfunction "GND_EXP@9") (pintype "power_in"))
      (node (ref "Q1") (pin "2") (pinfunction "GND_2") (pintype "power_in"))
      (node (ref "R1") (pin "1") (pinfunction "1_1") (pintype "passive"))
      (node (ref "R10") (pin "1") (pinfunction "1_1") (pintype "passive"))
      (node (ref "R2") (pin "1") (pinfunction "1_1") (pintype "passive"))
      (node (ref "R4") (pin "1") (pinfunction "1_1") (pintype "passive"))
      (node (ref "R5") (pin "1") (pinfunction "1_1") (pintype "passive"))
      (node (ref "TP1") (pin "2") (pinfunction "2_2") (pintype "passive"))
      (node (ref "TP2") (pin "2") (pinfunction "2_2") (pintype "passive"))
      (node (ref "TP3") (pin "2") (pinfunction "2_2") (pintype "passive"))
      (node (ref "TP4") (pin "2") (pinfunction "2_2") (pintype "passive"))
      (node (ref "TP5") (pin "2") (pinfunction "2_2") (pintype "passive"))
      (node (ref "X1") (pin "1") (pinfunction "1_1") (pintype "passive"))
      (node (ref "X2") (pin "5") (pinfunction "GND_5") (pintype "bidirectional"))
      (node (ref "X2") (pin "SHD1") (pinfunction "SHD1_SHD1") (pintype "bidirectional"))
      (node (ref "X2") (pin "SHD2") (pinfunction "SHD2_SHD2") (pintype "bidirectional"))
      (node (ref "X2") (pin "SHD3") (pinfunction "SHD3_SHD3") (pintype "bidirectional"))
      (node (ref "X2") (pin "SHD4") (pinfunction "SHD4_SHD4") (pintype "bidirectional"))
      (node (ref "X3") (pin "6") (pinfunction "6_6") (pintype "passive"))
    )
    (net (code "38") (name "Net-(C8-Pad1)") (class "Default")
      (node (ref "C8") (pin "1") (pinfunction "1_1") (pintype "passive"))
      (node (ref "C9") (pin "2") (pinfunction "2_2") (pintype "passive"))
      (node (ref "R7") (pin "1") (pinfunction "1_1") (pintype "passive"))
    )
    (net (code "39") (name "Net-(C11-Pad1)") (class "Default")
      (node (ref "C11") (pin "1") (pinfunction "1_1") (pintype "passive"))
      (node (ref "R8") (pin "1") (pinfunction "1_1") (pintype "passive"))
    )
    (net (code "40") (name "Net-(C18-Pad1)") (class "Default")
      (node (ref "C18") (pin "1") (pinfunction "1_1") (pintype "passive"))
      (node (ref "R11") (pin "1") (pinfunction "1_1") (pintype "passive"))
    )
    (net (code "41") (name "Net-(IC1-LL)") (class "Default")
      (node (ref "C10") (pin "2") (pinfunction "2_2") (pintype "passive"))
      (node (ref "IC1") (pin "10") (pinfunction "LL_6_10") (pintype "output"))
      (node (ref "IC1") (pin "11") (pinfunction "LL_11") (pintype "output"))
      (node (ref "IC1") (pin "6") (pinfunction "LL_2_6") (pintype "output"))
      (node (ref "IC1") (pin "7") (pinfunction "LL_3_7") (pintype "output"))
      (node (ref "IC1") (pin "8") (pinfunction "LL_4_8") (pintype "output"))
      (node (ref "IC1") (pin "9") (pinfunction "LL_5_9") (pintype "output"))
      (node (ref "L1") (pin "2") (pinfunction "2_2") (pintype "passive"))
      (node (ref "R7") (pin "2") (pinfunction "2_2") (pintype "passive"))
      (node (ref "R8") (pin "2") (pinfunction "2_2") (pintype "passive"))
    )
    (net (code "42") (name "Net-(IC1-MODE)") (class "Default")
      (node (ref "IC1") (pin "20") (pinfunction "MODE_20") (pintype "input"))
      (node (ref "R1") (pin "2") (pinfunction "2_2") (pintype "passive"))
    )
    (net (code "43") (name "Net-(IC1-TRIP)") (class "Default")
      (node (ref "IC1") (pin "21") (pinfunction "TRIP_21") (pintype "input"))
      (node (ref "R2") (pin "2") (pinfunction "2_2") (pintype "passive"))
    )
    (net (code "44") (name "Net-(IC1-VBST)") (class "Default")
      (node (ref "C10") (pin "1") (pinfunction "1_1") (pintype "passive"))
      (node (ref "IC1") (pin "4") (pinfunction "VBST_4") (pintype "input"))
    )
    (net (code "45") (name "Net-(IC1-VREG)") (class "Default")
      (node (ref "C6") (pin "1") (pinfunction "1_1") (pintype "passive"))
      (node (ref "IC1") (pin "18") (pinfunction "VREG_18") (pintype "power_in"))
    )
    (net (code "46") (name "Net-(IC2-PadCOMP)") (class "Default")
      (node (ref "IC2") (pin "COMP") (pinfunction "COMP_COMP") (pintype "bidirectional"))
      (node (ref "R11") (pin "2") (pinfunction "2_2") (pintype "passive"))
    )
    (net (code "47") (name "Net-(IC2-PadEN)") (class "Default")
      (node (ref "IC2") (pin "EN") (pinfunction "EN_EN") (pintype "bidirectional"))
      (node (ref "R12") (pin "1") (pinfunction "1_1") (pintype "passive"))
    )
    (net (code "48") (name "Net-(IC2-PadFB)") (class "Default")
      (node (ref "IC2") (pin "FB") (pinfunction "FB_FB") (pintype "bidirectional"))
      (node (ref "R10") (pin "2") (pinfunction "2_2") (pintype "passive"))
      (node (ref "R9") (pin "1") (pinfunction "1_1") (pintype "passive"))
    )
    (net (code "49") (name "Net-(IC2-PadLX)") (class "Default")
      (node (ref "IC2") (pin "LX") (pinfunction "LX_LX") (pintype "bidirectional"))
      (node (ref "L2") (pin "1") (pinfunction "1_1") (pintype "passive"))
    )
    (net (code "50") (name "Net-(IC5-D+)") (class "Default")
      (node (ref "IC5") (pin "4") (pinfunction "D+_4") (pintype "bidirectional"))
      (node (ref "X2") (pin "3") (pinfunction "D+_3") (pintype "bidirectional"))
    )
    (net (code "51") (name "Net-(IC5-D-)") (class "Default")
      (node (ref "IC5") (pin "5") (pinfunction "D-_5") (pintype "bidirectional"))
      (node (ref "X2") (pin "2") (pinfunction "D-_2") (pintype "bidirectional"))
    )
    (net (code "52") (name "Net-(IC5-VBUS)") (class "Default")
      (node (ref "IC5") (pin "8") (pinfunction "VBUS_8") (pintype "input"))
      (node (ref "X2") (pin "1") (pinfunction "+5V_1") (pintype "bidirectional"))
    )
    (net (code "53") (name "Net-(IC5-~{RST})") (class "Default")
      (node (ref "IC5") (pin "9") (pinfunction "~{RST}_9") (pintype "bidirectional"))
      (node (ref "R13") (pin "1") (pinfunction "1_1") (pintype "passive"))
    )
    (net (code "54") (name "Net-(IC6-AREF)") (class "Default")
      (node (ref "C30") (pin "2") (pinfunction "2_2") (pintype "passive"))
      (node (ref "IC6") (pin "20") (pinfunction "AREF_20") (pintype "passive"))
    )
    (net (code "55") (name "Net-(IC6-PB6(XTAL1{slash}TOSC1{slash}PCINT6))") (class "Default")
      (node (ref "C31") (pin "1") (pinfunction "1_1") (pintype "passive"))
      (node (ref "IC6") (pin "7") (pinfunction "PB6(XTAL1/TOSC1/PCINT6)_7") (pintype "bidirectional"))
      (node (ref "Q2") (pin "2") (pinfunction "2_2") (pintype "passive"))
    )
    (net (code "56") (name "Net-(IC6-PB7(XTAL2{slash}TOSC2{slash}PCINT7))") (class "Default")
      (node (ref "C32") (pin "1") (pinfunction "1_1") (pintype "passive"))
      (node (ref "IC6") (pin "8") (pinfunction "PB7(XTAL2/TOSC2/PCINT7)_8") (pintype "bidirectional"))
      (node (ref "Q2") (pin "1") (pinfunction "1_1") (pintype "passive"))
    )
    (net (code "57") (name "Net-(IC12A-G1)") (class "Default")
      (node (ref "IC12") (pin "6") (pinfunction "G1_6") (pintype "input"))
      (node (ref "IC6") (pin "29") (pinfunction "PC6(/RESET/PCINT14)_29") (pintype "bidirectional"))
      (node (ref "R14") (pin "1") (pinfunction "1_1") (pintype "passive"))
      (node (ref "X3") (pin "5") (pinfunction "5_5") (pintype "passive"))
    )
    (net (code "58") (name "unconnected-(IC1-N{slash}C-Pad5)") (class "Default")
      (node (ref "IC1") (pin "5") (pinfunction "N/C_5") (pintype "passive"))
    )
    (net (code "59") (name "unconnected-(IC1-PGOOD-Pad3)") (class "Default")
      (node (ref "IC1") (pin "3") (pinfunction "PGOOD_3") (pintype "output"))
    )
    (net (code "60") (name "unconnected-(IC1-RF-Pad22)") (class "Default")
      (node (ref "IC1") (pin "22") (pinfunction "RF_22") (pintype "input"))
    )
    (net (code "61") (name "unconnected-(IC3-BYP-Pad4)") (class "Default")
      (node (ref "IC3") (pin "4") (pinfunction "BYP_4") (pintype "bidirectional"))
    )
    (net (code "62") (name "unconnected-(IC4-BYP-Pad4)") (class "Default")
      (node (ref "IC4") (pin "4") (pinfunction "BYP_4") (pintype "bidirectional"))
    )
    (net (code "63") (name "unconnected-(IC5-CTS-Pad23)") (class "Default")
      (node (ref "IC5") (pin "23") (pinfunction "CTS_23") (pintype "input"))
    )
    (net (code "64") (name "unconnected-(IC5-DCD-Pad1)") (class "Default")
      (node (ref "IC5") (pin "1") (pinfunction "DCD_1") (pintype "input"))
    )
    (net (code "65") (name "unconnected-(IC5-DSR-Pad27)") (class "Default")
      (node (ref "IC5") (pin "27") (pinfunction "DSR_27") (pintype "input"))
    )
    (net (code "66") (name "unconnected-(IC5-DTR-Pad28)") (class "Default")
      (node (ref "IC5") (pin "28") (pinfunction "DTR_28") (pintype "output"))
    )
    (net (code "67") (name "unconnected-(IC5-RI-Pad2)") (class "Default")
      (node (ref "IC5") (pin "2") (pinfunction "RI_2") (pintype "input"))
    )
    (net (code "68") (name "unconnected-(IC5-RTS-Pad24)") (class "Default")
      (node (ref "IC5") (pin "24") (pinfunction "RTS_24") (pintype "output"))
    )
    (net (code "69") (name "unconnected-(IC5-SUSPEND-Pad12)") (class "Default")
      (node (ref "IC5") (pin "12") (pinfunction "SUSPEND_12") (pintype "output"))
    )
    (net (code "70") (name "unconnected-(IC5-~{SUSPEND}-Pad11)") (class "Default")
      (node (ref "IC5") (pin "11") (pinfunction "~{SUSPEND}_11") (pintype "output"))
    )
    (net (code "71") (name "unconnected-(IC6-ADC6-Pad19)") (class "Default")
      (node (ref "IC6") (pin "19") (pinfunction "ADC6_19") (pintype "passive"))
    )
    (net (code "72") (name "unconnected-(IC6-ADC7-Pad22)") (class "Default")
      (node (ref "IC6") (pin "22") (pinfunction "ADC7_22") (pintype "passive"))
    )
    (net (code "73") (name "unconnected-(IC12A-Y4-Pad11)") (class "Default")
      (node (ref "IC12") (pin "11") (pinfunction "Y4_11") (pintype "output"))
    )
    (net (code "74") (name "unconnected-(IC12A-Y5-Pad10)") (class "Default")
      (node (ref "IC12") (pin "10") (pinfunction "Y5_10") (pintype "output"))
    )
    (net (code "75") (name "unconnected-(IC12A-Y6-Pad9)") (class "Default")
      (node (ref "IC12") (pin "9") (pinfunction "Y6_9") (pintype "output"))
    )
    (net (code "76") (name "unconnected-(IC12A-Y7-Pad7)") (class "Default")
      (node (ref "IC12") (pin "7") (pinfunction "Y7_7") (pintype "output"))
    )
    (net (code "77") (name "unconnected-(X2-NC-Pad4)") (class "Default")
      (node (ref "X2") (pin "4") (pinfunction "NC_4") (pintype "bidirectional"))
    )
  )
)
